# ArduinoDevBoardRevA.net
KiCad netlist of a schematic drawn in EAGLE
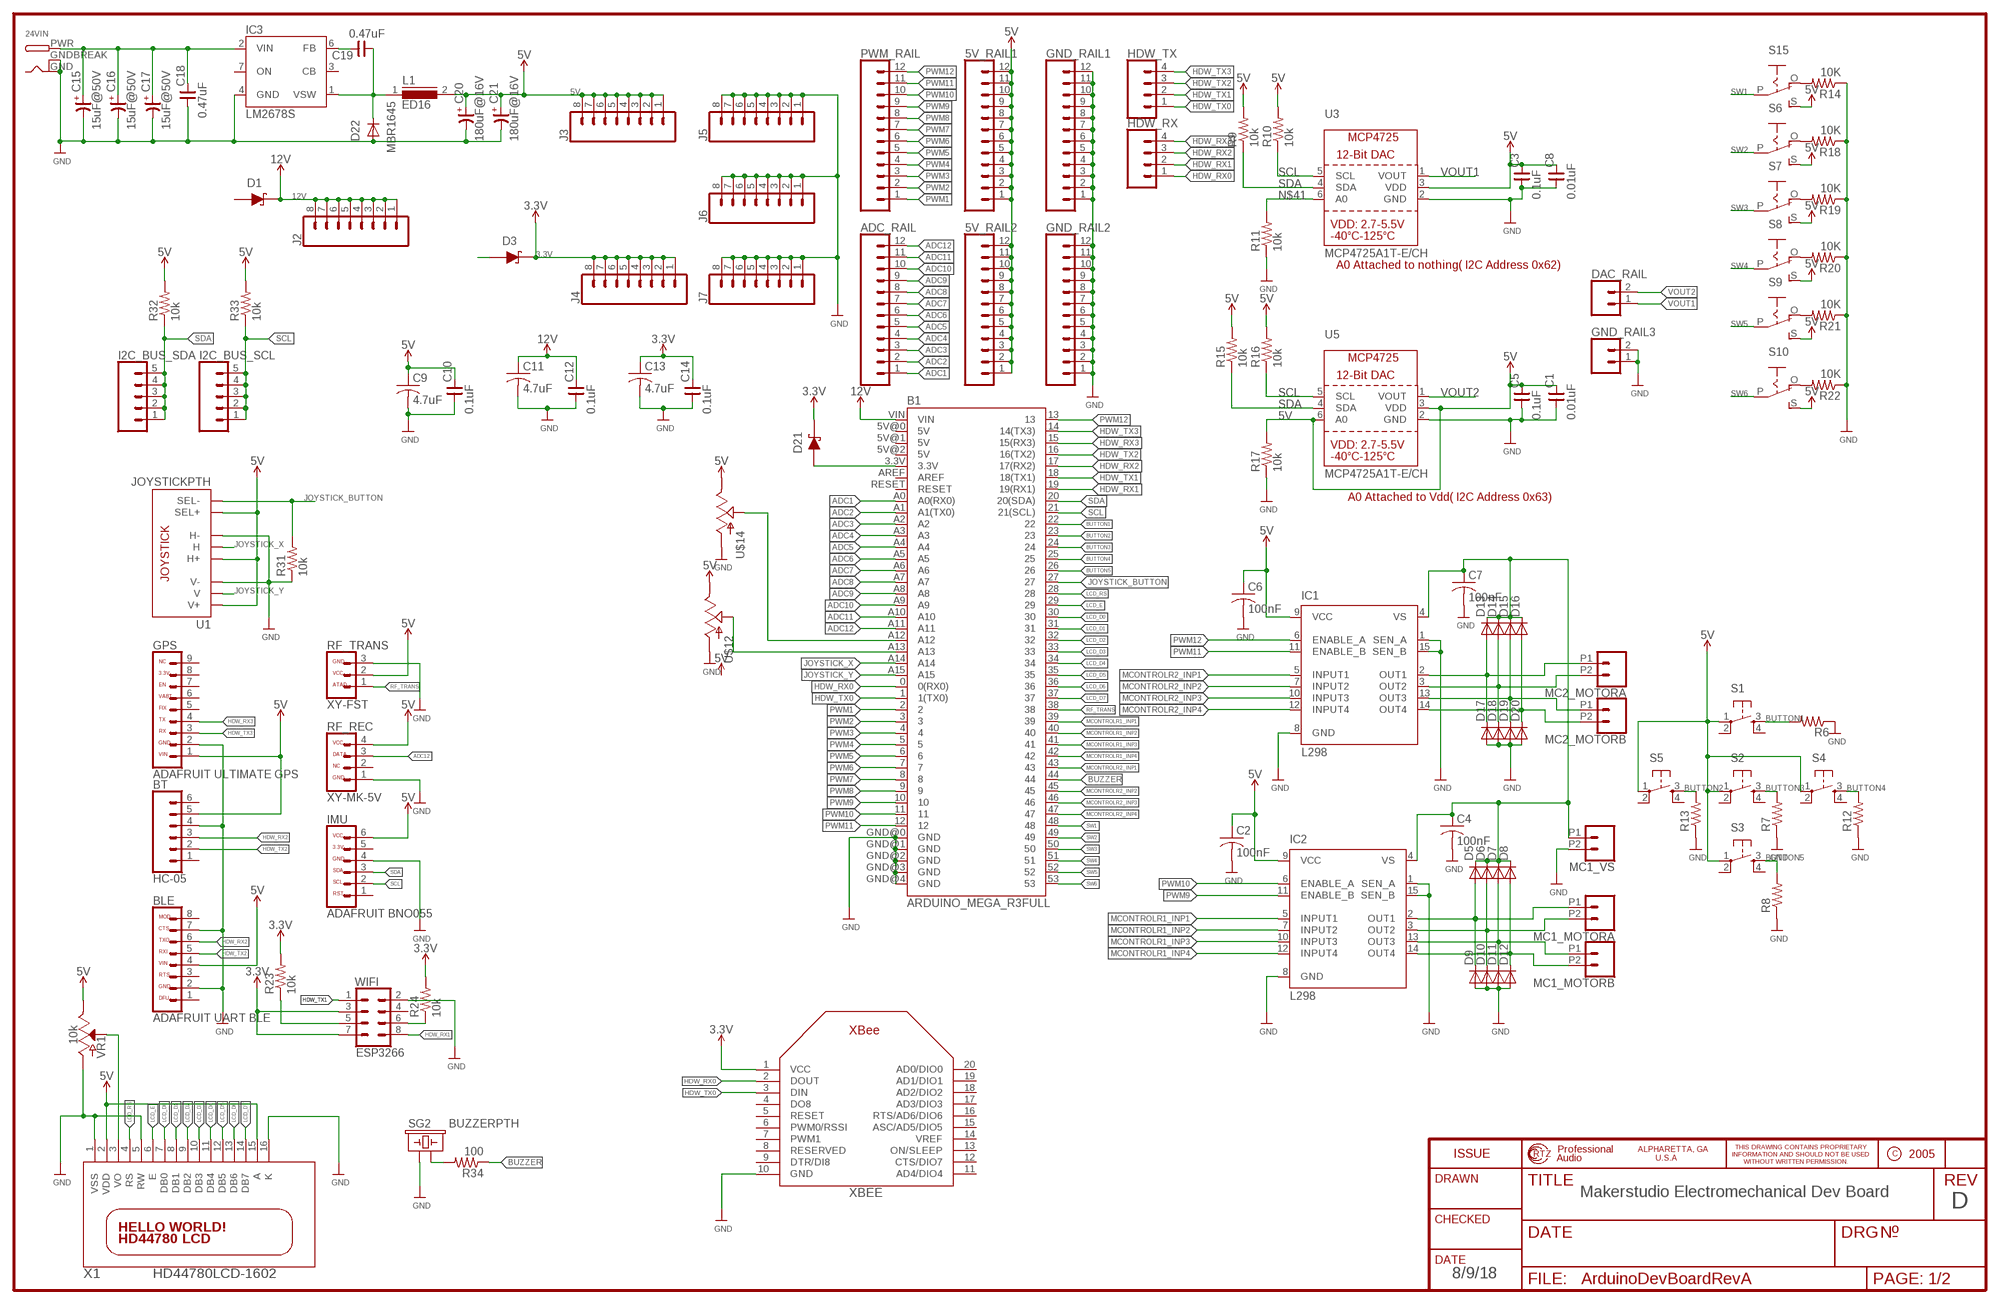
[diagram p0: schematic, sheet 1]
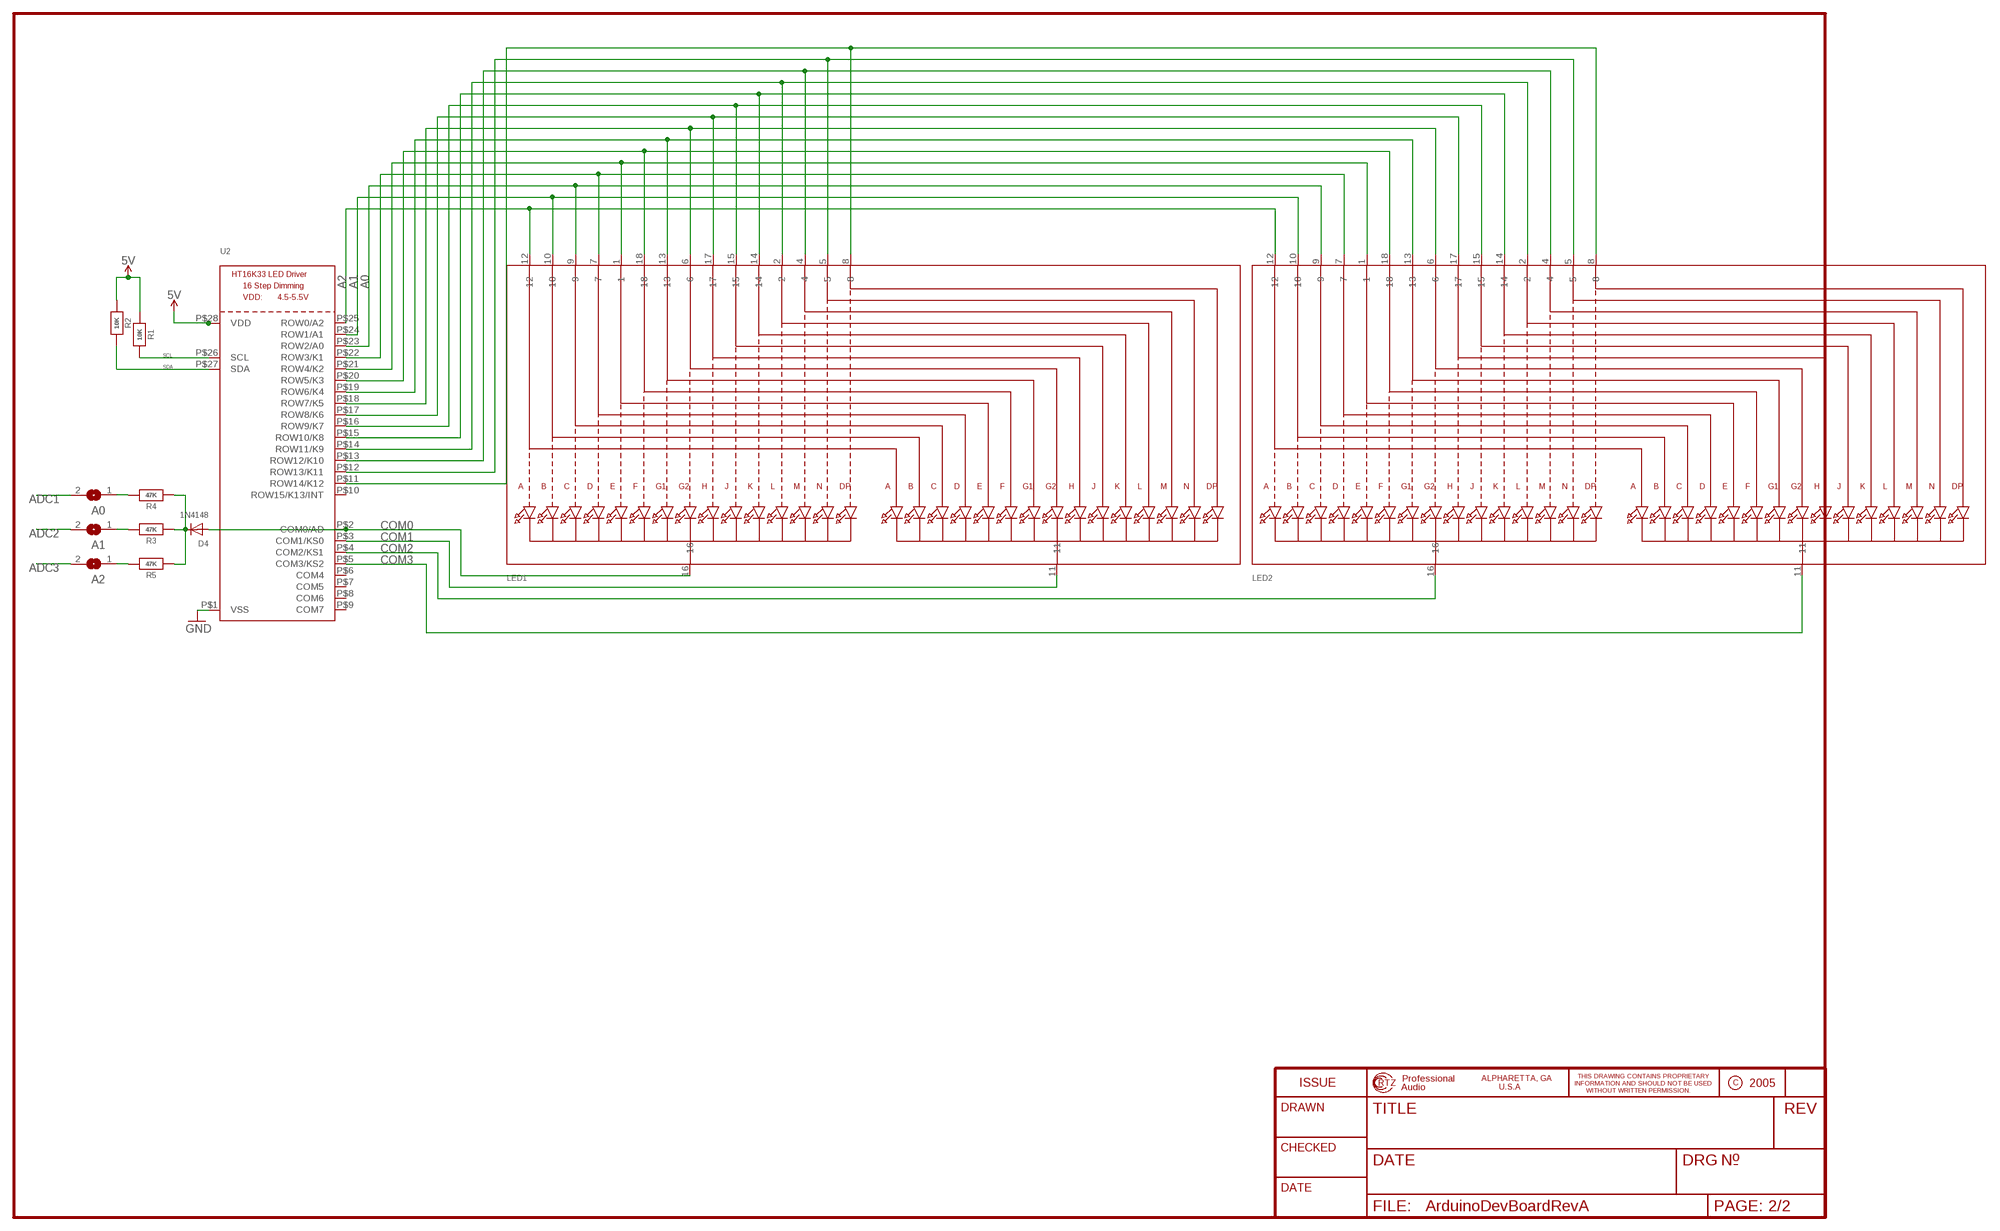
[diagram p1: schematic, sheet 2]

(export (version "E")
  (design (tool "Eeschema 10.0.6"))
  (components
    (comp (ref "5V_RAIL1")
      (value "CONN_12")
      (footprint "eagle-import:1X12")
      (libsource (lib "eagle-import") (part "CONN_12"))
    )
    (comp (ref "5V_RAIL2")
      (value "CONN_12")
      (footprint "eagle-import:1X12")
      (libsource (lib "eagle-import") (part "CONN_12"))
    )
    (comp (ref "24VIN")
      (value "DCBARRELPTH")
      (footprint "eagle-import:DCJACK_2MM_PTH")
      (libsource (lib "eagle-import") (part "DCBARRELPTH"))
    )
    (comp (ref "ADC_RAIL")
      (value "CONN_12")
      (footprint "eagle-import:1X12")
      (libsource (lib "eagle-import") (part "CONN_12"))
    )
    (comp (ref "B1")
      (value "ARDUINO_MEGA_R3FULL")
      (footprint "eagle-import:ARDUINO_MEGA")
      (libsource (lib "eagle-import") (part "ARDUINO_MEGA_R3FULL"))
    )
    (comp (ref "BLE")
      (value "ADAFRUIT UART BLE")
      (footprint "eagle-import:1X08")
      (libsource (lib "eagle-import") (part "CONN_08{dblquote}"))
    )
    (comp (ref "BT")
      (value "HC-05")
      (footprint "eagle-import:1X06")
      (libsource (lib "eagle-import") (part "CONN_06SILK_FEMALE_PTH"))
    )
    (comp (ref "C1")
      (value "0.01uF")
      (footprint "eagle-import:0805")
      (libsource (lib "eagle-import") (part "CNP-0805"))
    )
    (comp (ref "C2")
      (value "100nF")
      (footprint "eagle-import:C050-024X044")
      (libsource (lib "eagle-import") (part "C-US050-024X044"))
    )
    (comp (ref "C3")
      (value "0.1uF")
      (footprint "eagle-import:0805")
      (libsource (lib "eagle-import") (part "CNP-0805"))
    )
    (comp (ref "C4")
      (value "100nF")
      (footprint "eagle-import:C050-024X044")
      (libsource (lib "eagle-import") (part "C-US050-024X044"))
    )
    (comp (ref "C5")
      (value "0.1uF")
      (footprint "eagle-import:0805")
      (libsource (lib "eagle-import") (part "CNP-0805"))
    )
    (comp (ref "C6")
      (value "100nF")
      (footprint "eagle-import:C050-024X044")
      (libsource (lib "eagle-import") (part "C-US050-024X044"))
    )
    (comp (ref "C7")
      (value "100nF")
      (footprint "eagle-import:C050-024X044")
      (libsource (lib "eagle-import") (part "C-US050-024X044"))
    )
    (comp (ref "C8")
      (value "0.01uF")
      (footprint "eagle-import:0805")
      (libsource (lib "eagle-import") (part "CNP-0805"))
    )
    (comp (ref "C9")
      (value "4.7uF")
      (footprint "eagle-import:C050-024X044")
      (libsource (lib "eagle-import") (part "C-US050-024X044"))
    )
    (comp (ref "C10")
      (value "0.1uF")
      (footprint "eagle-import:0805")
      (libsource (lib "eagle-import") (part "CNP-0805"))
    )
    (comp (ref "C11")
      (value "4.7uF")
      (footprint "eagle-import:C0805")
      (libsource (lib "eagle-import") (part "C-USC0805"))
    )
    (comp (ref "C12")
      (value "0.1uF")
      (footprint "eagle-import:0805")
      (libsource (lib "eagle-import") (part "CNP-0805"))
    )
    (comp (ref "C13")
      (value "4.7uF")
      (footprint "eagle-import:C0805")
      (libsource (lib "eagle-import") (part "C-USC0805"))
    )
    (comp (ref "C14")
      (value "0.1uF")
      (footprint "eagle-import:0805")
      (libsource (lib "eagle-import") (part "CNP-0805"))
    )
    (comp (ref "C15")
      (value "15uF@50V")
      (footprint "eagle-import:E-025X065")
      (libsource (lib "eagle-import") (part "CP-E-025X065"))
    )
    (comp (ref "C16")
      (value "15uF@50V")
      (footprint "eagle-import:E-025X065")
      (libsource (lib "eagle-import") (part "CP-E-025X065"))
    )
    (comp (ref "C17")
      (value "15uF@50V")
      (footprint "eagle-import:E-025X065")
      (libsource (lib "eagle-import") (part "CP-E-025X065"))
    )
    (comp (ref "C18")
      (value "0.47uF")
      (footprint "eagle-import:0805")
      (libsource (lib "eagle-import") (part "CNP-0805"))
    )
    (comp (ref "C19")
      (value "0.47uF")
      (footprint "eagle-import:0805")
      (libsource (lib "eagle-import") (part "CNP-0805"))
    )
    (comp (ref "C20")
      (value "180uF@16V")
      (footprint "eagle-import:E-025X065")
      (libsource (lib "eagle-import") (part "CP-E-025X065"))
    )
    (comp (ref "C21")
      (value "180uF@16V")
      (footprint "eagle-import:E-025X065")
      (libsource (lib "eagle-import") (part "CP-E-025X065"))
    )
    (comp (ref "D1")
      (value "D_SCHOTTKYK")
      (footprint "eagle-import:SOD-123")
      (libsource (lib "eagle-import") (part "D_SCHOTTKYK"))
    )
    (comp (ref "D3")
      (value "D_SCHOTTKYK")
      (footprint "eagle-import:SOD-123")
      (libsource (lib "eagle-import") (part "D_SCHOTTKYK"))
    )
    (comp (ref "D5")
      (value "DIODE-D-5")
      (footprint "eagle-import:D-5")
      (libsource (lib "eagle-import") (part "DIODE-D-5"))
    )
    (comp (ref "D6")
      (value "DIODE-D-5")
      (footprint "eagle-import:D-5")
      (libsource (lib "eagle-import") (part "DIODE-D-5"))
    )
    (comp (ref "D7")
      (value "DIODE-D-5")
      (footprint "eagle-import:D-5")
      (libsource (lib "eagle-import") (part "DIODE-D-5"))
    )
    (comp (ref "D8")
      (value "DIODE-D-5")
      (footprint "eagle-import:D-5")
      (libsource (lib "eagle-import") (part "DIODE-D-5"))
    )
    (comp (ref "D9")
      (value "DIODE-D-5")
      (footprint "eagle-import:D-5")
      (libsource (lib "eagle-import") (part "DIODE-D-5"))
    )
    (comp (ref "D10")
      (value "DIODE-D-5")
      (footprint "eagle-import:D-5")
      (libsource (lib "eagle-import") (part "DIODE-D-5"))
    )
    (comp (ref "D11")
      (value "DIODE-D-5")
      (footprint "eagle-import:D-5")
      (libsource (lib "eagle-import") (part "DIODE-D-5"))
    )
    (comp (ref "D12")
      (value "DIODE-D-5")
      (footprint "eagle-import:D-5")
      (libsource (lib "eagle-import") (part "DIODE-D-5"))
    )
    (comp (ref "D13")
      (value "DIODE-D-5")
      (footprint "eagle-import:D-5")
      (libsource (lib "eagle-import") (part "DIODE-D-5"))
    )
    (comp (ref "D14")
      (value "DIODE-D-5")
      (footprint "eagle-import:D-5")
      (libsource (lib "eagle-import") (part "DIODE-D-5"))
    )
    (comp (ref "D15")
      (value "DIODE-D-5")
      (footprint "eagle-import:D-5")
      (libsource (lib "eagle-import") (part "DIODE-D-5"))
    )
    (comp (ref "D16")
      (value "DIODE-D-5")
      (footprint "eagle-import:D-5")
      (libsource (lib "eagle-import") (part "DIODE-D-5"))
    )
    (comp (ref "D17")
      (value "DIODE-D-5")
      (footprint "eagle-import:D-5")
      (libsource (lib "eagle-import") (part "DIODE-D-5"))
    )
    (comp (ref "D18")
      (value "DIODE-D-5")
      (footprint "eagle-import:D-5")
      (libsource (lib "eagle-import") (part "DIODE-D-5"))
    )
    (comp (ref "D19")
      (value "DIODE-D-5")
      (footprint "eagle-import:D-5")
      (libsource (lib "eagle-import") (part "DIODE-D-5"))
    )
    (comp (ref "D20")
      (value "DIODE-D-5")
      (footprint "eagle-import:D-5")
      (libsource (lib "eagle-import") (part "DIODE-D-5"))
    )
    (comp (ref "D21")
      (value "D_SCHOTTKYK")
      (footprint "eagle-import:SOD-123")
      (libsource (lib "eagle-import") (part "D_SCHOTTKYK"))
    )
    (comp (ref "D22")
      (value "MBR1645")
      (footprint "eagle-import:TO220AC")
      (libsource (lib "eagle-import") (part "MBR750"))
    )
    (comp (ref "DAC_RAIL")
      (value "CONN_02")
      (footprint "eagle-import:1X02")
      (libsource (lib "eagle-import") (part "CONN_02"))
    )
    (comp (ref "GND_RAIL1")
      (value "CONN_12")
      (footprint "eagle-import:1X12")
      (libsource (lib "eagle-import") (part "CONN_12"))
    )
    (comp (ref "GND_RAIL2")
      (value "CONN_12")
      (footprint "eagle-import:1X12")
      (libsource (lib "eagle-import") (part "CONN_12"))
    )
    (comp (ref "GND_RAIL3")
      (value "CONN_02")
      (footprint "eagle-import:1X02")
      (libsource (lib "eagle-import") (part "CONN_02"))
    )
    (comp (ref "GPS")
      (value "ADAFRUIT ULTIMATE GPS")
      (footprint "eagle-import:1X09")
      (libsource (lib "eagle-import") (part "CONN_09"))
    )
    (comp (ref "HDW_RX")
      (value "CONN_04")
      (footprint "eagle-import:1X04")
      (libsource (lib "eagle-import") (part "SparkFun-Connectors_513_CONN_04"))
    )
    (comp (ref "HDW_TX")
      (value "CONN_04")
      (footprint "eagle-import:1X04")
      (libsource (lib "eagle-import") (part "SparkFun-Connectors_513_CONN_04"))
    )
    (comp (ref "I2C_BUS_SCL")
      (value "CONN_05")
      (footprint "eagle-import:1X05")
      (libsource (lib "eagle-import") (part "CONN_05"))
    )
    (comp (ref "I2C_BUS_SDA")
      (value "CONN_05")
      (footprint "eagle-import:1X05")
      (libsource (lib "eagle-import") (part "CONN_05"))
    )
    (comp (ref "IC1")
      (value "L298")
      (footprint "eagle-import:MULTIWATT-15")
      (fields (field (name "MPN") "L298N"))
      (libsource (lib "eagle-import") (part "L298"))
    )
    (comp (ref "IC2")
      (value "L298")
      (footprint "eagle-import:MULTIWATT-15")
      (fields (field (name "MPN") "L298N"))
      (libsource (lib "eagle-import") (part "L298"))
    )
    (comp (ref "IC3")
      (value "LM2678S")
      (footprint "eagle-import:TO263-7")
      (libsource (lib "eagle-import") (part "LM2678S"))
    )
    (comp (ref "IMU")
      (value "ADAFRUIT BNO055")
      (footprint "eagle-import:1X06")
      (libsource (lib "eagle-import") (part "SparkFun-Connectors_513_CONN_06SILK_FEMALE_PTH"))
    )
    (comp (ref "J2")
      (value "CONN_08\"")
      (footprint "eagle-import:1X08")
      (libsource (lib "eagle-import") (part "CONN_08{dblquote}"))
    )
    (comp (ref "J3")
      (value "CONN_08\"")
      (footprint "eagle-import:1X08")
      (libsource (lib "eagle-import") (part "CONN_08{dblquote}"))
    )
    (comp (ref "J4")
      (value "CONN_08\"")
      (footprint "eagle-import:1X08")
      (libsource (lib "eagle-import") (part "CONN_08{dblquote}"))
    )
    (comp (ref "J5")
      (value "CONN_08\"")
      (footprint "eagle-import:1X08")
      (libsource (lib "eagle-import") (part "CONN_08{dblquote}"))
    )
    (comp (ref "J6")
      (value "CONN_08\"")
      (footprint "eagle-import:1X08")
      (libsource (lib "eagle-import") (part "CONN_08{dblquote}"))
    )
    (comp (ref "J7")
      (value "CONN_08\"")
      (footprint "eagle-import:1X08")
      (libsource (lib "eagle-import") (part "CONN_08{dblquote}"))
    )
    (comp (ref "L1")
      (value "ED16")
      (footprint "eagle-import:ED16")
      (libsource (lib "eagle-import") (part "ED16"))
    )
    (comp (ref "MC1_MOTORA")
      (value "CONN_022.54MM_SCREWTERM")
      (footprint "eagle-import:1X02_2.54_SCREWTERM")
      (libsource (lib "eagle-import") (part "CONN_022.54MM_SCREWTERM"))
    )
    (comp (ref "MC1_MOTORB")
      (value "CONN_022.54MM_SCREWTERM")
      (footprint "eagle-import:1X02_2.54_SCREWTERM")
      (libsource (lib "eagle-import") (part "CONN_022.54MM_SCREWTERM"))
    )
    (comp (ref "MC1_VS")
      (value "CONN_022.54MM_SCREWTERM")
      (footprint "eagle-import:1X02_2.54_SCREWTERM")
      (libsource (lib "eagle-import") (part "CONN_022.54MM_SCREWTERM"))
    )
    (comp (ref "MC2_MOTORA")
      (value "CONN_022.54MM_SCREWTERM")
      (footprint "eagle-import:1X02_2.54_SCREWTERM")
      (libsource (lib "eagle-import") (part "CONN_022.54MM_SCREWTERM"))
    )
    (comp (ref "MC2_MOTORB")
      (value "CONN_022.54MM_SCREWTERM")
      (footprint "eagle-import:1X02_2.54_SCREWTERM")
      (libsource (lib "eagle-import") (part "CONN_022.54MM_SCREWTERM"))
    )
    (comp (ref "PWM_RAIL")
      (value "CONN_12")
      (footprint "eagle-import:1X12")
      (libsource (lib "eagle-import") (part "CONN_12"))
    )
    (comp (ref "R6")
      (value "R-US_R0805")
      (footprint "eagle-import:R0805")
      (libsource (lib "eagle-import") (part "R-US_R0805"))
    )
    (comp (ref "R7")
      (value "R-US_R0805")
      (footprint "eagle-import:R0805")
      (libsource (lib "eagle-import") (part "R-US_R0805"))
    )
    (comp (ref "R8")
      (value "R-US_R0805")
      (footprint "eagle-import:R0805")
      (libsource (lib "eagle-import") (part "R-US_R0805"))
    )
    (comp (ref "R9")
      (value "10k")
      (footprint "eagle-import:R0805")
      (libsource (lib "eagle-import") (part "R-US_R0805"))
    )
    (comp (ref "R10")
      (value "10k")
      (footprint "eagle-import:R0805")
      (libsource (lib "eagle-import") (part "R-US_R0805"))
    )
    (comp (ref "R11")
      (value "10k")
      (footprint "eagle-import:R0805")
      (libsource (lib "eagle-import") (part "R-US_R0805"))
    )
    (comp (ref "R12")
      (value "R-US_R0805")
      (footprint "eagle-import:R0805")
      (libsource (lib "eagle-import") (part "R-US_R0805"))
    )
    (comp (ref "R13")
      (value "R-US_R0805")
      (footprint "eagle-import:R0805")
      (libsource (lib "eagle-import") (part "R-US_R0805"))
    )
    (comp (ref "R14")
      (value "10K")
      (footprint "eagle-import:R0805")
      (libsource (lib "eagle-import") (part "R-US_R0805"))
    )
    (comp (ref "R15")
      (value "10k")
      (footprint "eagle-import:R0805")
      (libsource (lib "eagle-import") (part "R-US_R0805"))
    )
    (comp (ref "R16")
      (value "10k")
      (footprint "eagle-import:R0805")
      (libsource (lib "eagle-import") (part "R-US_R0805"))
    )
    (comp (ref "R17")
      (value "10k")
      (footprint "eagle-import:R0805")
      (libsource (lib "eagle-import") (part "R-US_R0805"))
    )
    (comp (ref "R18")
      (value "10K")
      (footprint "eagle-import:R0805")
      (libsource (lib "eagle-import") (part "R-US_R0805"))
    )
    (comp (ref "R19")
      (value "10K")
      (footprint "eagle-import:R0805")
      (libsource (lib "eagle-import") (part "R-US_R0805"))
    )
    (comp (ref "R20")
      (value "10K")
      (footprint "eagle-import:R0805")
      (libsource (lib "eagle-import") (part "R-US_R0805"))
    )
    (comp (ref "R21")
      (value "10K")
      (footprint "eagle-import:R0805")
      (libsource (lib "eagle-import") (part "R-US_R0805"))
    )
    (comp (ref "R22")
      (value "10K")
      (footprint "eagle-import:R0805")
      (libsource (lib "eagle-import") (part "R-US_R0805"))
    )
    (comp (ref "R23")
      (value "10k")
      (footprint "eagle-import:R0805")
      (libsource (lib "eagle-import") (part "R-US_R0805"))
    )
    (comp (ref "R24")
      (value "10k")
      (footprint "eagle-import:R0805")
      (libsource (lib "eagle-import") (part "R-US_R0805"))
    )
    (comp (ref "R31")
      (value "10k")
      (footprint "eagle-import:R0805")
      (libsource (lib "eagle-import") (part "R-US_R0805"))
    )
    (comp (ref "R32")
      (value "10k")
      (footprint "eagle-import:R0805")
      (libsource (lib "eagle-import") (part "R-US_R0805"))
    )
    (comp (ref "R33")
      (value "10k")
      (footprint "eagle-import:R0805")
      (libsource (lib "eagle-import") (part "R-US_R0805"))
    )
    (comp (ref "R34")
      (value "100")
      (footprint "eagle-import:R0805")
      (libsource (lib "eagle-import") (part "R-US_R0805"))
    )
    (comp (ref "RF_REC")
      (value "XY-MK-5V")
      (footprint "eagle-import:1X04")
      (libsource (lib "eagle-import") (part "CONN_04"))
    )
    (comp (ref "RF_TRANS")
      (value "XY-FST")
      (footprint "eagle-import:1X03")
      (libsource (lib "eagle-import") (part "CONN_03"))
    )
    (comp (ref "S1")
      (value "TAC_SWITCHSMD")
      (footprint "eagle-import:TACTILE_SWITCH_SMD")
      (libsource (lib "eagle-import") (part "TAC_SWITCHSMD"))
    )
    (comp (ref "S2")
      (value "TAC_SWITCHSMD")
      (footprint "eagle-import:TACTILE_SWITCH_SMD")
      (libsource (lib "eagle-import") (part "TAC_SWITCHSMD"))
    )
    (comp (ref "S3")
      (value "TAC_SWITCHSMD")
      (footprint "eagle-import:TACTILE_SWITCH_SMD")
      (libsource (lib "eagle-import") (part "TAC_SWITCHSMD"))
    )
    (comp (ref "S4")
      (value "TAC_SWITCHSMD")
      (footprint "eagle-import:TACTILE_SWITCH_SMD")
      (libsource (lib "eagle-import") (part "TAC_SWITCHSMD"))
    )
    (comp (ref "S5")
      (value "TAC_SWITCHSMD")
      (footprint "eagle-import:TACTILE_SWITCH_SMD")
      (libsource (lib "eagle-import") (part "TAC_SWITCHSMD"))
    )
    (comp (ref "S6")
      (value "EG1218S")
      (footprint "eagle-import:EG1218")
      (libsource (lib "eagle-import") (part "EG1218S"))
    )
    (comp (ref "S7")
      (value "EG1218S")
      (footprint "eagle-import:EG1218")
      (libsource (lib "eagle-import") (part "EG1218S"))
    )
    (comp (ref "S8")
      (value "EG1218S")
      (footprint "eagle-import:EG1218")
      (libsource (lib "eagle-import") (part "EG1218S"))
    )
    (comp (ref "S9")
      (value "EG1218S")
      (footprint "eagle-import:EG1218")
      (libsource (lib "eagle-import") (part "EG1218S"))
    )
    (comp (ref "S10")
      (value "EG1218S")
      (footprint "eagle-import:EG1218")
      (libsource (lib "eagle-import") (part "EG1218S"))
    )
    (comp (ref "S15")
      (value "EG1218S")
      (footprint "eagle-import:EG1218")
      (libsource (lib "eagle-import") (part "EG1218S"))
    )
    (comp (ref "SG2")
      (value "BUZZERPTH")
      (footprint "eagle-import:BUZZER-12MM")
      (libsource (lib "eagle-import") (part "BUZZERPTH"))
    )
    (comp (ref "U$12")
      (value "POT")
      (footprint "eagle-import:ALPS_POT")
      (libsource (lib "eagle-import") (part "POT"))
    )
    (comp (ref "U$14")
      (value "POT")
      (footprint "eagle-import:ALPS_POT")
      (libsource (lib "eagle-import") (part "POT"))
    )
    (comp (ref "U1")
      (value "JOYSTICKPTH")
      (footprint "eagle-import:JOYSTICK")
      (libsource (lib "eagle-import") (part "JOYSTICKPTH"))
    )
    (comp (ref "U3")
      (value "MCP4725A1T-E/CH")
      (footprint "eagle-import:SOT23-6")
      (libsource (lib "eagle-import") (part "DAC_MCP4725"))
    )
    (comp (ref "U5")
      (value "MCP4725A1T-E/CH")
      (footprint "eagle-import:SOT23-6")
      (libsource (lib "eagle-import") (part "DAC_MCP4725"))
    )
    (comp (ref "VR1")
      (value "10k")
      (footprint "eagle-import:POT-PTH-ALPS-KIT")
      (libsource (lib "eagle-import") (part "POTENTIOMETER-PTH-9MM-1/20W-20%-KIT"))
    )
    (comp (ref "WIFI")
      (value "ESP3266")
      (footprint "eagle-import:2X4")
      (libsource (lib "eagle-import") (part "CONN_04X2"))
    )
    (comp (ref "X1")
      (value "HD44780LCD-1602")
      (footprint "eagle-import:LCD1602")
      (libsource (lib "eagle-import") (part "HD44780LCD-1602"))
    )
    (comp (ref "XBEE")
      (value "XBEE")
      (footprint "eagle-import:XBEE")
      (libsource (lib "eagle-import") (part "XBEE"))
    )
    (comp (ref "A0")
      (value "SOLDERJUMPERREFLOW_NOPASTE")
      (footprint "eagle-import:SOLDERJUMPER_REFLOW_NOPASTE")
      (libsource (lib "eagle-import") (part "SOLDERJUMPERREFLOW_NOPASTE"))
    )
    (comp (ref "A1")
      (value "SOLDERJUMPERREFLOW_NOPASTE")
      (footprint "eagle-import:SOLDERJUMPER_REFLOW_NOPASTE")
      (libsource (lib "eagle-import") (part "SOLDERJUMPERREFLOW_NOPASTE"))
    )
    (comp (ref "A2")
      (value "SOLDERJUMPERREFLOW_NOPASTE")
      (footprint "eagle-import:SOLDERJUMPER_REFLOW_NOPASTE")
      (libsource (lib "eagle-import") (part "SOLDERJUMPERREFLOW_NOPASTE"))
    )
    (comp (ref "D4")
      (value "1N4148")
      (footprint "eagle-import:SOD-323F")
      (libsource (lib "eagle-import") (part "DIODESOD-323F"))
    )
    (comp (ref "LED1")
      (value "DISP_SEGMENT_STARBURST_DUAL_COMMONCATHODE")
      (footprint "eagle-import:SEGMENT_STARTBUST_DUAL_KWA-541CBB")
      (libsource (lib "eagle-import") (part "DISP_SEGMENT_STARBURST_DUAL_COMMONCATHODE"))
    )
    (comp (ref "LED2")
      (value "DISP_SEGMENT_STARBURST_DUAL_COMMONCATHODE")
      (footprint "eagle-import:SEGMENT_STARTBUST_DUAL_KWA-541CBB")
      (libsource (lib "eagle-import") (part "DISP_SEGMENT_STARBURST_DUAL_COMMONCATHODE"))
    )
    (comp (ref "R1")
      (value "10K")
      (footprint "eagle-import:0805-NO")
      (libsource (lib "eagle-import") (part "RESISTOR0805_NOOUTLINE"))
    )
    (comp (ref "R2")
      (value "10K")
      (footprint "eagle-import:0805-NO")
      (libsource (lib "eagle-import") (part "RESISTOR0805_NOOUTLINE"))
    )
    (comp (ref "R3")
      (value "47K")
      (footprint "eagle-import:0805-NO")
      (libsource (lib "eagle-import") (part "RESISTOR0805_NOOUTLINE"))
    )
    (comp (ref "R4")
      (value "47K")
      (footprint "eagle-import:0805-NO")
      (libsource (lib "eagle-import") (part "RESISTOR0805_NOOUTLINE"))
    )
    (comp (ref "R5")
      (value "47K")
      (footprint "eagle-import:0805-NO")
      (libsource (lib "eagle-import") (part "RESISTOR0805_NOOUTLINE"))
    )
    (comp (ref "U2")
      (value "HT16K33_SOP28")
      (footprint "eagle-import:SOP28_300MIL")
      (libsource (lib "eagle-import") (part "HT16K33_SOP28"))
    )
  )
  (nets
    (net (code "1") (name "3.3V") (class "Default")
      (node (ref "C13") (pin "1") (pinfunction "1_1") (pintype "passive"))
      (node (ref "C14") (pin "2") (pinfunction "2_2") (pintype "passive"))
      (node (ref "D21") (pin "2") (pinfunction "C_2") (pintype "passive"))
      (node (ref "D3") (pin "2") (pinfunction "C_2") (pintype "passive"))
      (node (ref "J4") (pin "1") (pinfunction "1_1") (pintype "passive"))
      (node (ref "J4") (pin "2") (pinfunction "2_2") (pintype "passive"))
      (node (ref "J4") (pin "3") (pinfunction "3_3") (pintype "passive"))
      (node (ref "J4") (pin "4") (pinfunction "4_4") (pintype "passive"))
      (node (ref "J4") (pin "5") (pinfunction "5_5") (pintype "passive"))
      (node (ref "J4") (pin "6") (pinfunction "6_6") (pintype "passive"))
      (node (ref "J4") (pin "7") (pinfunction "7_7") (pintype "passive"))
      (node (ref "J4") (pin "8") (pinfunction "8_8") (pintype "passive"))
      (node (ref "R23") (pin "2") (pinfunction "2_2") (pintype "passive"))
      (node (ref "R24") (pin "2") (pinfunction "2_2") (pintype "passive"))
      (node (ref "WIFI") (pin "3") (pinfunction "3_3") (pintype "passive"))
      (node (ref "WIFI") (pin "7") (pinfunction "7_7") (pintype "passive"))
      (node (ref "XBEE") (pin "1") (pinfunction "VCC_1") (pintype "power_in"))
    )
    (net (code "2") (name "5V") (class "Default")
      (node (ref "5V_RAIL1") (pin "1") (pinfunction "1_1") (pintype "passive"))
      (node (ref "5V_RAIL1") (pin "10") (pinfunction "10_10") (pintype "passive"))
      (node (ref "5V_RAIL1") (pin "11") (pinfunction "11_11") (pintype "passive"))
      (node (ref "5V_RAIL1") (pin "12") (pinfunction "12_12") (pintype "passive"))
      (node (ref "5V_RAIL1") (pin "2") (pinfunction "2_2") (pintype "passive"))
      (node (ref "5V_RAIL1") (pin "3") (pinfunction "3_3") (pintype "passive"))
      (node (ref "5V_RAIL1") (pin "4") (pinfunction "4_4") (pintype "passive"))
      (node (ref "5V_RAIL1") (pin "5") (pinfunction "5_5") (pintype "passive"))
      (node (ref "5V_RAIL1") (pin "6") (pinfunction "6_6") (pintype "passive"))
      (node (ref "5V_RAIL1") (pin "7") (pinfunction "7_7") (pintype "passive"))
      (node (ref "5V_RAIL1") (pin "8") (pinfunction "8_8") (pintype "passive"))
      (node (ref "5V_RAIL1") (pin "9") (pinfunction "9_9") (pintype "passive"))
      (node (ref "5V_RAIL2") (pin "1") (pinfunction "1_1") (pintype "passive"))
      (node (ref "5V_RAIL2") (pin "10") (pinfunction "10_10") (pintype "passive"))
      (node (ref "5V_RAIL2") (pin "11") (pinfunction "11_11") (pintype "passive"))
      (node (ref "5V_RAIL2") (pin "12") (pinfunction "12_12") (pintype "passive"))
      (node (ref "5V_RAIL2") (pin "2") (pinfunction "2_2") (pintype "passive"))
      (node (ref "5V_RAIL2") (pin "3") (pinfunction "3_3") (pintype "passive"))
      (node (ref "5V_RAIL2") (pin "4") (pinfunction "4_4") (pintype "passive"))
      (node (ref "5V_RAIL2") (pin "5") (pinfunction "5_5") (pintype "passive"))
      (node (ref "5V_RAIL2") (pin "6") (pinfunction "6_6") (pintype "passive"))
      (node (ref "5V_RAIL2") (pin "7") (pinfunction "7_7") (pintype "passive"))
      (node (ref "5V_RAIL2") (pin "8") (pinfunction "8_8") (pintype "passive"))
      (node (ref "5V_RAIL2") (pin "9") (pinfunction "9_9") (pintype "passive"))
      (node (ref "BLE") (pin "4") (pinfunction "4_4") (pintype "passive"))
      (node (ref "BT") (pin "5") (pinfunction "5_5") (pintype "passive"))
      (node (ref "C1") (pin "2") (pinfunction "2_2") (pintype "passive"))
      (node (ref "C10") (pin "2") (pinfunction "2_2") (pintype "passive"))
      (node (ref "C2") (pin "1") (pinfunction "1_1") (pintype "passive"))
      (node (ref "C20") (pin "+") (pinfunction "+_+") (pintype "passive"))
      (node (ref "C21") (pin "+") (pinfunction "+_+") (pintype "passive"))
      (node (ref "C3") (pin "2") (pinfunction "2_2") (pintype "passive"))
      (node (ref "C5") (pin "2") (pinfunction "2_2") (pintype "passive"))
      (node (ref "C6") (pin "1") (pinfunction "1_1") (pintype "passive"))
      (node (ref "C8") (pin "2") (pinfunction "2_2") (pintype "passive"))
      (node (ref "C9") (pin "1") (pinfunction "1_1") (pintype "passive"))
      (node (ref "GPS") (pin "1") (pinfunction "1_1") (pintype "passive"))
      (node (ref "IC1") (pin "9") (pinfunction "VCC_9") (pintype "power_in"))
      (node (ref "IC2") (pin "9") (pinfunction "VCC_9") (pintype "power_in"))
      (node (ref "IMU") (pin "6") (pinfunction "6_6") (pintype "passive"))
      (node (ref "J3") (pin "1") (pinfunction "1_1") (pintype "passive"))
      (node (ref "J3") (pin "2") (pinfunction "2_2") (pintype "passive"))
      (node (ref "J3") (pin "3") (pinfunction "3_3") (pintype "passive"))
      (node (ref "J3") (pin "4") (pinfunction "4_4") (pintype "passive"))
      (node (ref "J3") (pin "5") (pinfunction "5_5") (pintype "passive"))
      (node (ref "J3") (pin "6") (pinfunction "6_6") (pintype "passive"))
      (node (ref "J3") (pin "7") (pinfunction "7_7") (pintype "passive"))
      (node (ref "J3") (pin "8") (pinfunction "8_8") (pintype "passive"))
      (node (ref "L1") (pin "2") (pinfunction "2_2") (pintype "passive"))
      (node (ref "R1") (pin "1") (pinfunction "1_1") (pintype "passive"))
      (node (ref "R10") (pin "2") (pinfunction "2_2") (pintype "passive"))
      (node (ref "R15") (pin "2") (pinfunction "2_2") (pintype "passive"))
      (node (ref "R16") (pin "2") (pinfunction "2_2") (pintype "passive"))
      (node (ref "R17") (pin "2") (pinfunction "2_2") (pintype "passive"))
      (node (ref "R2") (pin "1") (pinfunction "1_1") (pintype "passive"))
      (node (ref "R32") (pin "2") (pinfunction "2_2") (pintype "passive"))
      (node (ref "R33") (pin "2") (pinfunction "2_2") (pintype "passive"))
      (node (ref "R9") (pin "2") (pinfunction "2_2") (pintype "passive"))
      (node (ref "RF_REC") (pin "4") (pinfunction "4_4") (pintype "passive"))
      (node (ref "RF_TRANS") (pin "2") (pinfunction "2_2") (pintype "passive"))
      (node (ref "S1") (pin "1") (pinfunction "1_1") (pintype "passive"))
      (node (ref "S10") (pin "S") (pinfunction "S_S") (pintype "passive"))
      (node (ref "S15") (pin "S") (pinfunction "S_S") (pintype "passive"))
      (node (ref "S2") (pin "1") (pinfunction "1_1") (pintype "passive"))
      (node (ref "S3") (pin "1") (pinfunction "1_1") (pintype "passive"))
      (node (ref "S4") (pin "1") (pinfunction "1_1") (pintype "passive"))
      (node (ref "S5") (pin "1") (pinfunction "1_1") (pintype "passive"))
      (node (ref "S6") (pin "S") (pinfunction "S_S") (pintype "passive"))
      (node (ref "S7") (pin "S") (pinfunction "S_S") (pintype "passive"))
      (node (ref "S8") (pin "S") (pinfunction "S_S") (pintype "passive"))
      (node (ref "S9") (pin "S") (pinfunction "S_S") (pintype "passive"))
      (node (ref "U$12") (pin "P$1") (pinfunction "E_P$1") (pintype "passive"))
      (node (ref "U$14") (pin "P$1") (pinfunction "E_P$1") (pintype "passive"))
      (node (ref "U1") (pin "B1A") (pinfunction "SEL+_B1A") (pintype "bidirectional"))
      (node (ref "U1") (pin "H1") (pinfunction "H+_H1") (pintype "bidirectional"))
      (node (ref "U1") (pin "V1") (pinfunction "V+_V1") (pintype "bidirectional"))
      (node (ref "U2") (pin "P$28") (pinfunction "VDD_P$28") (pintype "bidirectional"))
      (node (ref "U3") (pin "3") (pinfunction "VDD_3") (pintype "power_in"))
      (node (ref "U5") (pin "3") (pinfunction "VDD_3") (pintype "power_in"))
      (node (ref "U5") (pin "6") (pinfunction "A0_6") (pintype "input"))
      (node (ref "VR1") (pin "P$1") (pinfunction "E_P$1") (pintype "passive"))
      (node (ref "X1") (pin "15") (pinfunction "A_15") (pintype "input"))
      (node (ref "X1") (pin "2") (pinfunction "VDD_2") (pintype "power_in"))
    )
    (net (code "3") (name "12V") (class "Default")
      (node (ref "B1") (pin "VIN") (pinfunction "VIN_VIN") (pintype "bidirectional"))
      (node (ref "C11") (pin "1") (pinfunction "1_1") (pintype "passive"))
      (node (ref "C12") (pin "2") (pinfunction "2_2") (pintype "passive"))
      (node (ref "D1") (pin "2") (pinfunction "C_2") (pintype "passive"))
      (node (ref "J2") (pin "1") (pinfunction "1_1") (pintype "passive"))
      (node (ref "J2") (pin "2") (pinfunction "2_2") (pintype "passive"))
      (node (ref "J2") (pin "3") (pinfunction "3_3") (pintype "passive"))
      (node (ref "J2") (pin "4") (pinfunction "4_4") (pintype "passive"))
      (node (ref "J2") (pin "5") (pinfunction "5_5") (pintype "passive"))
      (node (ref "J2") (pin "6") (pinfunction "6_6") (pintype "passive"))
      (node (ref "J2") (pin "7") (pinfunction "7_7") (pintype "passive"))
      (node (ref "J2") (pin "8") (pinfunction "8_8") (pintype "passive"))
    )
    (net (code "4") (name "A0") (class "Default")
      (node (ref "LED1") (pin "9") (pinfunction "9_9") (pintype "bidirectional"))
      (node (ref "LED2") (pin "9") (pinfunction "9_9") (pintype "bidirectional"))
      (node (ref "U2") (pin "P$23") (pinfunction "ROW2/A0_P$23") (pintype "bidirectional"))
    )
    (net (code "5") (name "A1") (class "Default")
      (node (ref "LED1") (pin "10") (pinfunction "10_10") (pintype "bidirectional"))
      (node (ref "LED2") (pin "10") (pinfunction "10_10") (pintype "bidirectional"))
      (node (ref "U2") (pin "P$24") (pinfunction "ROW1/A1_P$24") (pintype "bidirectional"))
    )
    (net (code "6") (name "A2") (class "Default")
      (node (ref "LED1") (pin "12") (pinfunction "12_12") (pintype "bidirectional"))
      (node (ref "LED2") (pin "12") (pinfunction "12_12") (pintype "bidirectional"))
      (node (ref "U2") (pin "P$25") (pinfunction "ROW0/A2_P$25") (pintype "bidirectional"))
    )
    (net (code "7") (name "ADC1") (class "Default")
      (node (ref "A0") (pin "2") (pinfunction "2_2") (pintype "passive"))
      (node (ref "ADC_RAIL") (pin "1") (pinfunction "1_1") (pintype "passive"))
      (node (ref "B1") (pin "A0") (pinfunction "A0(RX0)_A0") (pintype "bidirectional"))
    )
    (net (code "8") (name "ADC2") (class "Default")
      (node (ref "A1") (pin "2") (pinfunction "2_2") (pintype "passive"))
      (node (ref "ADC_RAIL") (pin "2") (pinfunction "2_2") (pintype "passive"))
      (node (ref "B1") (pin "A1") (pinfunction "A1(TX0)_A1") (pintype "bidirectional"))
    )
    (net (code "9") (name "ADC3") (class "Default")
      (node (ref "A2") (pin "2") (pinfunction "2_2") (pintype "passive"))
      (node (ref "ADC_RAIL") (pin "3") (pinfunction "3_3") (pintype "passive"))
      (node (ref "B1") (pin "A2") (pinfunction "A2_A2") (pintype "bidirectional"))
    )
    (net (code "10") (name "ADC4") (class "Default")
      (node (ref "ADC_RAIL") (pin "4") (pinfunction "4_4") (pintype "passive"))
      (node (ref "B1") (pin "A3") (pinfunction "A3_A3") (pintype "bidirectional"))
    )
    (net (code "11") (name "ADC5") (class "Default")
      (node (ref "ADC_RAIL") (pin "5") (pinfunction "5_5") (pintype "passive"))
      (node (ref "B1") (pin "A4") (pinfunction "A4_A4") (pintype "bidirectional"))
    )
    (net (code "12") (name "ADC6") (class "Default")
      (node (ref "ADC_RAIL") (pin "6") (pinfunction "6_6") (pintype "passive"))
      (node (ref "B1") (pin "A5") (pinfunction "A5_A5") (pintype "bidirectional"))
    )
    (net (code "13") (name "ADC7") (class "Default")
      (node (ref "ADC_RAIL") (pin "7") (pinfunction "7_7") (pintype "passive"))
      (node (ref "B1") (pin "A6") (pinfunction "A6_A6") (pintype "bidirectional"))
    )
    (net (code "14") (name "ADC8") (class "Default")
      (node (ref "ADC_RAIL") (pin "8") (pinfunction "8_8") (pintype "passive"))
      (node (ref "B1") (pin "A7") (pinfunction "A7_A7") (pintype "bidirectional"))
    )
    (net (code "15") (name "ADC9") (class "Default")
      (node (ref "ADC_RAIL") (pin "9") (pinfunction "9_9") (pintype "passive"))
      (node (ref "B1") (pin "A8") (pinfunction "A8_A8") (pintype "bidirectional"))
    )
    (net (code "16") (name "ADC10") (class "Default")
      (node (ref "ADC_RAIL") (pin "10") (pinfunction "10_10") (pintype "passive"))
      (node (ref "B1") (pin "A9") (pinfunction "A9_A9") (pintype "bidirectional"))
    )
    (net (code "17") (name "ADC11") (class "Default")
      (node (ref "ADC_RAIL") (pin "11") (pinfunction "11_11") (pintype "passive"))
      (node (ref "B1") (pin "A10") (pinfunction "A10_A10") (pintype "bidirectional"))
    )
    (net (code "18") (name "ADC12") (class "Default")
      (node (ref "ADC_RAIL") (pin "12") (pinfunction "12_12") (pintype "passive"))
      (node (ref "B1") (pin "A11") (pinfunction "A11_A11") (pintype "bidirectional"))
      (node (ref "RF_REC") (pin "3") (pinfunction "3_3") (pintype "passive"))
    )
    (net (code "19") (name "BUTTON1") (class "Default")
      (node (ref "B1") (pin "22") (pinfunction "22_22") (pintype "bidirectional"))
      (node (ref "R6") (pin "2") (pinfunction "2_2") (pintype "passive"))
      (node (ref "S1") (pin "3") (pinfunction "3_3") (pintype "passive"))
    )
    (net (code "20") (name "BUTTON2") (class "Default")
      (node (ref "B1") (pin "23") (pinfunction "23_23") (pintype "bidirectional"))
      (node (ref "R13") (pin "2") (pinfunction "2_2") (pintype "passive"))
      (node (ref "S5") (pin "3") (pinfunction "3_3") (pintype "passive"))
    )
    (net (code "21") (name "BUTTON3") (class "Default")
      (node (ref "B1") (pin "24") (pinfunction "24_24") (pintype "bidirectional"))
      (node (ref "R7") (pin "2") (pinfunction "2_2") (pintype "passive"))
      (node (ref "S2") (pin "3") (pinfunction "3_3") (pintype "passive"))
    )
    (net (code "22") (name "BUTTON4") (class "Default")
      (node (ref "B1") (pin "25") (pinfunction "25_25") (pintype "bidirectional"))
      (node (ref "R12") (pin "2") (pinfunction "2_2") (pintype "passive"))
      (node (ref "S4") (pin "3") (pinfunction "3_3") (pintype "passive"))
    )
    (net (code "23") (name "BUTTON5") (class "Default")
      (node (ref "B1") (pin "26") (pinfunction "26_26") (pintype "bidirectional"))
      (node (ref "R8") (pin "2") (pinfunction "2_2") (pintype "passive"))
      (node (ref "S3") (pin "3") (pinfunction "3_3") (pintype "passive"))
    )
    (net (code "24") (name "BUZZER") (class "Default")
      (node (ref "B1") (pin "44") (pinfunction "44_44") (pintype "bidirectional"))
      (node (ref "R34") (pin "1") (pinfunction "1_1") (pintype "passive"))
    )
    (net (code "25") (name "COM0") (class "Default")
      (node (ref "D4") (pin "A") (pinfunction "A_A") (pintype "passive"))
      (node (ref "LED1") (pin "16") (pinfunction "16_16") (pintype "bidirectional"))
      (node (ref "U2") (pin "P$2") (pinfunction "COM0/AD_P$2") (pintype "bidirectional"))
    )
    (net (code "26") (name "COM1") (class "Default")
      (node (ref "LED1") (pin "11") (pinfunction "11_11") (pintype "bidirectional"))
      (node (ref "U2") (pin "P$3") (pinfunction "COM1/KS0_P$3") (pintype "bidirectional"))
    )
    (net (code "27") (name "COM2") (class "Default")
      (node (ref "LED2") (pin "16") (pinfunction "16_16") (pintype "bidirectional"))
      (node (ref "U2") (pin "P$4") (pinfunction "COM2/KS1_P$4") (pintype "bidirectional"))
    )
    (net (code "28") (name "COM3") (class "Default")
      (node (ref "LED2") (pin "11") (pinfunction "11_11") (pintype "bidirectional"))
      (node (ref "U2") (pin "P$5") (pinfunction "COM3/KS2_P$5") (pintype "bidirectional"))
    )
    (net (code "29") (name "GND") (class "Default")
      (node (ref "24VIN") (pin "GND") (pinfunction "GND_GND") (pintype "power_in"))
      (node (ref "24VIN") (pin "GNDBREAK") (pinfunction "GNDBREAK_GNDBREAK") (pintype "power_in"))
      (node (ref "B1") (pin "GND@0") (pinfunction "GND_GND@0") (pintype "bidirectional"))
      (node (ref "B1") (pin "GND@1") (pinfunction "GND_GND@1") (pintype "bidirectional"))
      (node (ref "B1") (pin "GND@2") (pinfunction "GND_GND@2") (pintype "bidirectional"))
      (node (ref "B1") (pin "GND@3") (pinfunction "GND_GND@3") (pintype "bidirectional"))
      (node (ref "B1") (pin "GND@4") (pinfunction "GND_GND@4") (pintype "bidirectional"))
      (node (ref "BLE") (pin "2") (pinfunction "2_2") (pintype "passive"))
      (node (ref "BLE") (pin "7") (pinfunction "7_7") (pintype "passive"))
      (node (ref "BT") (pin "4") (pinfunction "4_4") (pintype "passive"))
      (node (ref "C1") (pin "1") (pinfunction "1_1") (pintype "passive"))
      (node (ref "C10") (pin "1") (pinfunction "1_1") (pintype "passive"))
      (node (ref "C11") (pin "2") (pinfunction "2_2") (pintype "passive"))
      (node (ref "C12") (pin "1") (pinfunction "1_1") (pintype "passive"))
      (node (ref "C13") (pin "2") (pinfunction "2_2") (pintype "passive"))
      (node (ref "C14") (pin "1") (pinfunction "1_1") (pintype "passive"))
      (node (ref "C15") (pin "-") (pinfunction "-_-") (pintype "passive"))
      (node (ref "C16") (pin "-") (pinfunction "-_-") (pintype "passive"))
      (node (ref "C17") (pin "-") (pinfunction "-_-") (pintype "passive"))
      (node (ref "C18") (pin "1") (pinfunction "1_1") (pintype "passive"))
      (node (ref "C2") (pin "2") (pinfunction "2_2") (pintype "passive"))
      (node (ref "C20") (pin "-") (pinfunction "-_-") (pintype "passive"))
      (node (ref "C21") (pin "-") (pinfunction "-_-") (pintype "passive"))
      (node (ref "C3") (pin "1") (pinfunction "1_1") (pintype "passive"))
      (node (ref "C4") (pin "2") (pinfunction "2_2") (pintype "passive"))
      (node (ref "C5") (pin "1") (pinfunction "1_1") (pintype "passive"))
      (node (ref "C6") (pin "2") (pinfunction "2_2") (pintype "passive"))
      (node (ref "C7") (pin "2") (pinfunction "2_2") (pintype "passive"))
      (node (ref "C8") (pin "1") (pinfunction "1_1") (pintype "passive"))
      (node (ref "C9") (pin "2") (pinfunction "2_2") (pintype "passive"))
      (node (ref "D10") (pin "A") (pinfunction "A_A") (pintype "passive"))
      (node (ref "D11") (pin "A") (pinfunction "A_A") (pintype "passive"))
      (node (ref "D12") (pin "A") (pinfunction "A_A") (pintype "passive"))
      (node (ref "D17") (pin "A") (pinfunction "A_A") (pintype "passive"))
      (node (ref "D18") (pin "A") (pinfunction "A_A") (pintype "passive"))
      (node (ref "D19") (pin "A") (pinfunction "A_A") (pintype "passive"))
      (node (ref "D20") (pin "A") (pinfunction "A_A") (pintype "passive"))
      (node (ref "D22") (pin "A") (pinfunction "A_A") (pintype "passive"))
      (node (ref "D9") (pin "A") (pinfunction "A_A") (pintype "passive"))
      (node (ref "GND_RAIL1") (pin "1") (pinfunction "1_1") (pintype "passive"))
      (node (ref "GND_RAIL1") (pin "10") (pinfunction "10_10") (pintype "passive"))
      (node (ref "GND_RAIL1") (pin "11") (pinfunction "11_11") (pintype "passive"))
      (node (ref "GND_RAIL1") (pin "12") (pinfunction "12_12") (pintype "passive"))
      (node (ref "GND_RAIL1") (pin "2") (pinfunction "2_2") (pintype "passive"))
      (node (ref "GND_RAIL1") (pin "3") (pinfunction "3_3") (pintype "passive"))
      (node (ref "GND_RAIL1") (pin "4") (pinfunction "4_4") (pintype "passive"))
      (node (ref "GND_RAIL1") (pin "5") (pinfunction "5_5") (pintype "passive"))
      (node (ref "GND_RAIL1") (pin "6") (pinfunction "6_6") (pintype "passive"))
      (node (ref "GND_RAIL1") (pin "7") (pinfunction "7_7") (pintype "passive"))
      (node (ref "GND_RAIL1") (pin "8") (pinfunction "8_8") (pintype "passive"))
      (node (ref "GND_RAIL1") (pin "9") (pinfunction "9_9") (pintype "passive"))
      (node (ref "GND_RAIL2") (pin "1") (pinfunction "1_1") (pintype "passive"))
      (node (ref "GND_RAIL2") (pin "10") (pinfunction "10_10") (pintype "passive"))
      (node (ref "GND_RAIL2") (pin "11") (pinfunction "11_11") (pintype "passive"))
      (node (ref "GND_RAIL2") (pin "12") (pinfunction "12_12") (pintype "passive"))
      (node (ref "GND_RAIL2") (pin "2") (pinfunction "2_2") (pintype "passive"))
      (node (ref "GND_RAIL2") (pin "3") (pinfunction "3_3") (pintype "passive"))
      (node (ref "GND_RAIL2") (pin "4") (pinfunction "4_4") (pintype "passive"))
      (node (ref "GND_RAIL2") (pin "5") (pinfunction "5_5") (pintype "passive"))
      (node (ref "GND_RAIL2") (pin "6") (pinfunction "6_6") (pintype "passive"))
      (node (ref "GND_RAIL2") (pin "7") (pinfunction "7_7") (pintype "passive"))
      (node (ref "GND_RAIL2") (pin "8") (pinfunction "8_8") (pintype "passive"))
      (node (ref "GND_RAIL2") (pin "9") (pinfunction "9_9") (pintype "passive"))
      (node (ref "GND_RAIL3") (pin "1") (pinfunction "1_1") (pintype "passive"))
      (node (ref "GND_RAIL3") (pin "2") (pinfunction "2_2") (pintype "passive"))
      (node (ref "GPS") (pin "2") (pinfunction "2_2") (pintype "passive"))
      (node (ref "IC1") (pin "1") (pinfunction "SEN_A_1") (pintype "input"))
      (node (ref "IC1") (pin "15") (pinfunction "SEN_B_15") (pintype "input"))
      (node (ref "IC1") (pin "8") (pinfunction "GND_8") (pintype "power_in"))
      (node (ref "IC2") (pin "1") (pinfunction "SEN_A_1") (pintype "input"))
      (node (ref "IC2") (pin "15") (pinfunction "SEN_B_15") (pintype "input"))
      (node (ref "IC2") (pin "8") (pinfunction "GND_8") (pintype "power_in"))
      (node (ref "IC3") (pin "4") (pinfunction "GND_4") (pintype "power_in"))
      (node (ref "IMU") (pin "4") (pinfunction "4_4") (pintype "passive"))
      (node (ref "J5") (pin "1") (pinfunction "1_1") (pintype "passive"))
      (node (ref "J5") (pin "2") (pinfunction "2_2") (pintype "passive"))
      (node (ref "J5") (pin "3") (pinfunction "3_3") (pintype "passive"))
      (node (ref "J5") (pin "4") (pinfunction "4_4") (pintype "passive"))
      (node (ref "J5") (pin "5") (pinfunction "5_5") (pintype "passive"))
      (node (ref "J5") (pin "6") (pinfunction "6_6") (pintype "passive"))
      (node (ref "J5") (pin "7") (pinfunction "7_7") (pintype "passive"))
      (node (ref "J5") (pin "8") (pinfunction "8_8") (pintype "passive"))
      (node (ref "J6") (pin "1") (pinfunction "1_1") (pintype "passive"))
      (node (ref "J6") (pin "2") (pinfunction "2_2") (pintype "passive"))
      (node (ref "J6") (pin "3") (pinfunction "3_3") (pintype "passive"))
      (node (ref "J6") (pin "4") (pinfunction "4_4") (pintype "passive"))
      (node (ref "J6") (pin "5") (pinfunction "5_5") (pintype "passive"))
      (node (ref "J6") (pin "6") (pinfunction "6_6") (pintype "passive"))
      (node (ref "J6") (pin "7") (pinfunction "7_7") (pintype "passive"))
      (node (ref "J6") (pin "8") (pinfunction "8_8") (pintype "passive"))
      (node (ref "J7") (pin "1") (pinfunction "1_1") (pintype "passive"))
      (node (ref "J7") (pin "2") (pinfunction "2_2") (pintype "passive"))
      (node (ref "J7") (pin "3") (pinfunction "3_3") (pintype "passive"))
      (node (ref "J7") (pin "4") (pinfunction "4_4") (pintype "passive"))
      (node (ref "J7") (pin "5") (pinfunction "5_5") (pintype "passive"))
      (node (ref "J7") (pin "6") (pinfunction "6_6") (pintype "passive"))
      (node (ref "J7") (pin "7") (pinfunction "7_7") (pintype "passive"))
      (node (ref "J7") (pin "8") (pinfunction "8_8") (pintype "passive"))
      (node (ref "MC1_VS") (pin "P2") (pinfunction "2_P2") (pintype "passive"))
      (node (ref "R11") (pin "1") (pinfunction "1_1") (pintype "passive"))
      (node (ref "R12") (pin "1") (pinfunction "1_1") (pintype "passive"))
      (node (ref "R13") (pin "1") (pinfunction "1_1") (pintype "passive"))
      (node (ref "R14") (pin "1") (pinfunction "1_1") (pintype "passive"))
      (node (ref "R17") (pin "1") (pinfunction "1_1") (pintype "passive"))
      (node (ref "R18") (pin "1") (pinfunction "1_1") (pintype "passive"))
      (node (ref "R19") (pin "1") (pinfunction "1_1") (pintype "passive"))
      (node (ref "R20") (pin "1") (pinfunction "1_1") (pintype "passive"))
      (node (ref "R21") (pin "1") (pinfunction "1_1") (pintype "passive"))
      (node (ref "R22") (pin "1") (pinfunction "1_1") (pintype "passive"))
      (node (ref "R31") (pin "1") (pinfunction "1_1") (pintype "passive"))
      (node (ref "R6") (pin "1") (pinfunction "1_1") (pintype "passive"))
      (node (ref "R7") (pin "1") (pinfunction "1_1") (pintype "passive"))
      (node (ref "R8") (pin "1") (pinfunction "1_1") (pintype "passive"))
      (node (ref "RF_REC") (pin "1") (pinfunction "1_1") (pintype "passive"))
      (node (ref "RF_TRANS") (pin "3") (pinfunction "3_3") (pintype "passive"))
      (node (ref "SG2") (pin "+") (pinfunction "1_+") (pintype "passive"))
      (node (ref "U$12") (pin "P$3") (pinfunction "A_P$3") (pintype "passive"))
      (node (ref "U$14") (pin "P$3") (pinfunction "A_P$3") (pintype "passive"))
      (node (ref "U1") (pin "H3") (pinfunction "H-_H3") (pintype "bidirectional"))
      (node (ref "U1") (pin "V3") (pinfunction "V-_V3") (pintype "bidirectional"))
      (node (ref "U2") (pin "P$1") (pinfunction "VSS_P$1") (pintype "bidirectional"))
      (node (ref "U3") (pin "2") (pinfunction "GND_2") (pintype "power_in"))
      (node (ref "U5") (pin "2") (pinfunction "GND_2") (pintype "power_in"))
      (node (ref "VR1") (pin "P$3") (pinfunction "A_P$3") (pintype "passive"))
      (node (ref "WIFI") (pin "2") (pinfunction "2_2") (pintype "passive"))
      (node (ref "X1") (pin "1") (pinfunction "VSS_1") (pintype "power_in"))
      (node (ref "X1") (pin "16") (pinfunction "K_16") (pintype "input"))
      (node (ref "X1") (pin "5") (pinfunction "RW_5") (pintype "input"))
      (node (ref "XBEE") (pin "10") (pinfunction "GND_10") (pintype "power_in"))
    )
    (net (code "30") (name "HDW_RX0") (class "Default")
      (node (ref "B1") (pin "0") (pinfunction "0(RX0)_0") (pintype "bidirectional"))
      (node (ref "HDW_RX") (pin "1") (pinfunction "1_1") (pintype "passive"))
      (node (ref "XBEE") (pin "2") (pinfunction "DOUT_2") (pintype "output"))
    )
    (net (code "31") (name "HDW_RX1") (class "Default")
      (node (ref "B1") (pin "19") (pinfunction "19(RX1)_19") (pintype "bidirectional"))
      (node (ref "HDW_RX") (pin "2") (pinfunction "2_2") (pintype "passive"))
      (node (ref "WIFI") (pin "8") (pinfunction "8_8") (pintype "passive"))
    )
    (net (code "32") (name "HDW_RX2") (class "Default")
      (node (ref "B1") (pin "17") (pinfunction "17(RX2)_17") (pintype "bidirectional"))
      (node (ref "BLE") (pin "6") (pinfunction "6_6") (pintype "passive"))
      (node (ref "BT") (pin "3") (pinfunction "3_3") (pintype "passive"))
      (node (ref "HDW_RX") (pin "3") (pinfunction "3_3") (pintype "passive"))
    )
    (net (code "33") (name "HDW_RX3") (class "Default")
      (node (ref "B1") (pin "15") (pinfunction "15(RX3)_15") (pintype "bidirectional"))
      (node (ref "GPS") (pin "4") (pinfunction "4_4") (pintype "passive"))
      (node (ref "HDW_RX") (pin "4") (pinfunction "4_4") (pintype "passive"))
    )
    (net (code "34") (name "HDW_TX0") (class "Default")
      (node (ref "B1") (pin "1") (pinfunction "1(TX0)_1") (pintype "bidirectional"))
      (node (ref "HDW_TX") (pin "1") (pinfunction "1_1") (pintype "passive"))
      (node (ref "XBEE") (pin "3") (pinfunction "DIN_3") (pintype "input"))
    )
    (net (code "35") (name "HDW_TX1") (class "Default")
      (node (ref "B1") (pin "18") (pinfunction "18(TX1)_18") (pintype "bidirectional"))
      (node (ref "HDW_TX") (pin "2") (pinfunction "2_2") (pintype "passive"))
      (node (ref "WIFI") (pin "1") (pinfunction "1_1") (pintype "passive"))
    )
    (net (code "36") (name "HDW_TX2") (class "Default")
      (node (ref "B1") (pin "16") (pinfunction "16(TX2)_16") (pintype "bidirectional"))
      (node (ref "BLE") (pin "5") (pinfunction "5_5") (pintype "passive"))
      (node (ref "BT") (pin "2") (pinfunction "2_2") (pintype "passive"))
      (node (ref "HDW_TX") (pin "3") (pinfunction "3_3") (pintype "passive"))
    )
    (net (code "37") (name "HDW_TX3") (class "Default")
      (node (ref "B1") (pin "14") (pinfunction "14(TX3)_14") (pintype "bidirectional"))
      (node (ref "GPS") (pin "3") (pinfunction "3_3") (pintype "passive"))
      (node (ref "HDW_TX") (pin "4") (pinfunction "4_4") (pintype "passive"))
    )
    (net (code "38") (name "JOYSTICK_BUTTON") (class "Default")
      (node (ref "B1") (pin "27") (pinfunction "27_27") (pintype "bidirectional"))
      (node (ref "R31") (pin "2") (pinfunction "2_2") (pintype "passive"))
      (node (ref "U1") (pin "B2A") (pinfunction "SEL-_B2A") (pintype "bidirectional"))
    )
    (net (code "39") (name "JOYSTICK_X") (class "Default")
      (node (ref "B1") (pin "A14") (pinfunction "A14_A14") (pintype "bidirectional"))
      (node (ref "U1") (pin "H2") (pinfunction "H_H2") (pintype "bidirectional"))
    )
    (net (code "40") (name "JOYSTICK_Y") (class "Default")
      (node (ref "B1") (pin "A15") (pinfunction "A15_A15") (pintype "bidirectional"))
      (node (ref "U1") (pin "V2") (pinfunction "V_V2") (pintype "bidirectional"))
    )
    (net (code "41") (name "LCD_D0") (class "Default")
      (node (ref "B1") (pin "30") (pinfunction "30_30") (pintype "bidirectional"))
      (node (ref "X1") (pin "7") (pinfunction "DB0_7") (pintype "bidirectional"))
    )
    (net (code "42") (name "LCD_D1") (class "Default")
      (node (ref "B1") (pin "31") (pinfunction "31_31") (pintype "bidirectional"))
      (node (ref "X1") (pin "8") (pinfunction "DB1_8") (pintype "bidirectional"))
    )
    (net (code "43") (name "LCD_D2") (class "Default")
      (node (ref "B1") (pin "32") (pinfunction "32_32") (pintype "bidirectional"))
      (node (ref "X1") (pin "9") (pinfunction "DB2_9") (pintype "bidirectional"))
    )
    (net (code "44") (name "LCD_D3") (class "Default")
      (node (ref "B1") (pin "33") (pinfunction "33_33") (pintype "bidirectional"))
      (node (ref "X1") (pin "10") (pinfunction "DB3_10") (pintype "bidirectional"))
    )
    (net (code "45") (name "LCD_D4") (class "Default")
      (node (ref "B1") (pin "34") (pinfunction "34_34") (pintype "bidirectional"))
      (node (ref "X1") (pin "11") (pinfunction "DB4_11") (pintype "bidirectional"))
    )
    (net (code "46") (name "LCD_D5") (class "Default")
      (node (ref "B1") (pin "35") (pinfunction "35_35") (pintype "bidirectional"))
      (node (ref "X1") (pin "12") (pinfunction "DB5_12") (pintype "bidirectional"))
    )
    (net (code "47") (name "LCD_D6") (class "Default")
      (node (ref "B1") (pin "36") (pinfunction "36_36") (pintype "bidirectional"))
      (node (ref "X1") (pin "13") (pinfunction "DB6_13") (pintype "bidirectional"))
    )
    (net (code "48") (name "LCD_D7") (class "Default")
      (node (ref "B1") (pin "37") (pinfunction "37_37") (pintype "bidirectional"))
      (node (ref "X1") (pin "14") (pinfunction "DB7_14") (pintype "bidirectional"))
    )
    (net (code "49") (name "LCD_E") (class "Default")
      (node (ref "B1") (pin "29") (pinfunction "29_29") (pintype "bidirectional"))
      (node (ref "X1") (pin "6") (pinfunction "E_6") (pintype "input"))
    )
    (net (code "50") (name "LCD_RS") (class "Default")
      (node (ref "B1") (pin "28") (pinfunction "28_28") (pintype "bidirectional"))
      (node (ref "X1") (pin "4") (pinfunction "RS_4") (pintype "input"))
    )
    (net (code "51") (name "MCONTROLR1_INP1") (class "Default")
      (node (ref "B1") (pin "39") (pinfunction "39_39") (pintype "bidirectional"))
      (node (ref "IC2") (pin "5") (pinfunction "INPUT1_5") (pintype "input"))
    )
    (net (code "52") (name "MCONTROLR1_INP2") (class "Default")
      (node (ref "B1") (pin "40") (pinfunction "40_40") (pintype "bidirectional"))
      (node (ref "IC2") (pin "7") (pinfunction "INPUT2_7") (pintype "input"))
    )
    (net (code "53") (name "MCONTROLR1_INP3") (class "Default")
      (node (ref "B1") (pin "41") (pinfunction "41_41") (pintype "bidirectional"))
      (node (ref "IC2") (pin "10") (pinfunction "INPUT3_10") (pintype "input"))
    )
    (net (code "54") (name "MCONTROLR1_INP4") (class "Default")
      (node (ref "B1") (pin "42") (pinfunction "42_42") (pintype "bidirectional"))
      (node (ref "IC2") (pin "12") (pinfunction "INPUT4_12") (pintype "input"))
    )
    (net (code "55") (name "MCONTROLR2_INP1") (class "Default")
      (node (ref "B1") (pin "43") (pinfunction "43_43") (pintype "bidirectional"))
      (node (ref "IC1") (pin "5") (pinfunction "INPUT1_5") (pintype "input"))
    )
    (net (code "56") (name "MCONTROLR2_INP2") (class "Default")
      (node (ref "B1") (pin "45") (pinfunction "45_45") (pintype "bidirectional"))
      (node (ref "IC1") (pin "7") (pinfunction "INPUT2_7") (pintype "input"))
    )
    (net (code "57") (name "MCONTROLR2_INP3") (class "Default")
      (node (ref "B1") (pin "46") (pinfunction "46_46") (pintype "bidirectional"))
      (node (ref "IC1") (pin "10") (pinfunction "INPUT3_10") (pintype "input"))
    )
    (net (code "58") (name "MCONTROLR2_INP4") (class "Default")
      (node (ref "B1") (pin "47") (pinfunction "47_47") (pintype "bidirectional"))
      (node (ref "IC1") (pin "12") (pinfunction "INPUT4_12") (pintype "input"))
    )
    (net (code "59") (name "N$41") (class "Default")
      (node (ref "R11") (pin "2") (pinfunction "2_2") (pintype "passive"))
      (node (ref "U3") (pin "6") (pinfunction "A0_6") (pintype "input"))
    )
    (net (code "60") (name "Net-(A0-Pad1)") (class "Default")
      (node (ref "A0") (pin "1") (pinfunction "1_1") (pintype "passive"))
      (node (ref "R4") (pin "2") (pinfunction "2_2") (pintype "passive"))
    )
    (net (code "61") (name "Net-(A1-Pad1)") (class "Default")
      (node (ref "A1") (pin "1") (pinfunction "1_1") (pintype "passive"))
      (node (ref "R3") (pin "2") (pinfunction "2_2") (pintype "passive"))
    )
    (net (code "62") (name "Net-(A2-Pad1)") (class "Default")
      (node (ref "A2") (pin "1") (pinfunction "1_1") (pintype "passive"))
      (node (ref "R5") (pin "2") (pinfunction "2_2") (pintype "passive"))
    )
    (net (code "63") (name "Net-(D4-PadC)") (class "Default")
      (node (ref "D4") (pin "C") (pinfunction "C_C") (pintype "passive"))
      (node (ref "R3") (pin "1") (pinfunction "1_1") (pintype "passive"))
      (node (ref "R4") (pin "1") (pinfunction "1_1") (pintype "passive"))
      (node (ref "R5") (pin "1") (pinfunction "1_1") (pintype "passive"))
    )
    (net (code "64") (name "Net-(D21-A)") (class "Default")
      (node (ref "B1") (pin "3.3V") (pinfunction "3.3V_3.3V") (pintype "bidirectional"))
      (node (ref "D21") (pin "1") (pinfunction "A_1") (pintype "passive"))
    )
    (net (code "65") (name "Net-(IC1-OUT1)") (class "Default")
      (node (ref "D13") (pin "A") (pinfunction "A_A") (pintype "passive"))
      (node (ref "D17") (pin "C") (pinfunction "C_C") (pintype "passive"))
      (node (ref "IC1") (pin "2") (pinfunction "OUT1_2") (pintype "output"))
      (node (ref "MC2_MOTORA") (pin "P1") (pinfunction "1_P1") (pintype "passive"))
    )
    (net (code "66") (name "Net-(IC1-OUT2)") (class "Default")
      (node (ref "D14") (pin "A") (pinfunction "A_A") (pintype "passive"))
      (node (ref "D18") (pin "C") (pinfunction "C_C") (pintype "passive"))
      (node (ref "IC1") (pin "3") (pinfunction "OUT2_3") (pintype "output"))
      (node (ref "MC2_MOTORA") (pin "P2") (pinfunction "2_P2") (pintype "passive"))
    )
    (net (code "67") (name "Net-(IC1-OUT3)") (class "Default")
      (node (ref "D15") (pin "A") (pinfunction "A_A") (pintype "passive"))
      (node (ref "D19") (pin "C") (pinfunction "C_C") (pintype "passive"))
      (node (ref "IC1") (pin "13") (pinfunction "OUT3_13") (pintype "output"))
      (node (ref "MC2_MOTORB") (pin "P1") (pinfunction "1_P1") (pintype "passive"))
    )
    (net (code "68") (name "Net-(IC1-OUT4)") (class "Default")
      (node (ref "D16") (pin "A") (pinfunction "A_A") (pintype "passive"))
      (node (ref "D20") (pin "C") (pinfunction "C_C") (pintype "passive"))
      (node (ref "IC1") (pin "14") (pinfunction "OUT4_14") (pintype "output"))
      (node (ref "MC2_MOTORB") (pin "P2") (pinfunction "2_P2") (pintype "passive"))
    )
    (net (code "69") (name "Net-(IC1-VS)") (class "Default")
      (node (ref "C4") (pin "1") (pinfunction "1_1") (pintype "passive"))
      (node (ref "C7") (pin "1") (pinfunction "1_1") (pintype "passive"))
      (node (ref "D13") (pin "C") (pinfunction "C_C") (pintype "passive"))
      (node (ref "D14") (pin "C") (pinfunction "C_C") (pintype "passive"))
      (node (ref "D15") (pin "C") (pinfunction "C_C") (pintype "passive"))
      (node (ref "D16") (pin "C") (pinfunction "C_C") (pintype "passive"))
      (node (ref "D5") (pin "C") (pinfunction "C_C") (pintype "passive"))
      (node (ref "D6") (pin "C") (pinfunction "C_C") (pintype "passive"))
      (node (ref "D7") (pin "C") (pinfunction "C_C") (pintype "passive"))
      (node (ref "D8") (pin "C") (pinfunction "C_C") (pintype "passive"))
      (node (ref "IC1") (pin "4") (pinfunction "VS_4") (pintype "power_in"))
      (node (ref "IC2") (pin "4") (pinfunction "VS_4") (pintype "power_in"))
      (node (ref "MC1_VS") (pin "P1") (pinfunction "1_P1") (pintype "passive"))
    )
    (net (code "70") (name "Net-(IC2-OUT1)") (class "Default")
      (node (ref "D5") (pin "A") (pinfunction "A_A") (pintype "passive"))
      (node (ref "D9") (pin "C") (pinfunction "C_C") (pintype "passive"))
      (node (ref "IC2") (pin "2") (pinfunction "OUT1_2") (pintype "output"))
      (node (ref "MC1_MOTORA") (pin "P1") (pinfunction "1_P1") (pintype "passive"))
    )
    (net (code "71") (name "Net-(IC2-OUT2)") (class "Default")
      (node (ref "D10") (pin "C") (pinfunction "C_C") (pintype "passive"))
      (node (ref "D6") (pin "A") (pinfunction "A_A") (pintype "passive"))
      (node (ref "IC2") (pin "3") (pinfunction "OUT2_3") (pintype "output"))
      (node (ref "MC1_MOTORA") (pin "P2") (pinfunction "2_P2") (pintype "passive"))
    )
    (net (code "72") (name "Net-(IC2-OUT3)") (class "Default")
      (node (ref "D11") (pin "C") (pinfunction "C_C") (pintype "passive"))
      (node (ref "D7") (pin "A") (pinfunction "A_A") (pintype "passive"))
      (node (ref "IC2") (pin "13") (pinfunction "OUT3_13") (pintype "output"))
      (node (ref "MC1_MOTORB") (pin "P1") (pinfunction "1_P1") (pintype "passive"))
    )
    (net (code "73") (name "Net-(IC2-OUT4)") (class "Default")
      (node (ref "D12") (pin "C") (pinfunction "C_C") (pintype "passive"))
      (node (ref "D8") (pin "A") (pinfunction "A_A") (pintype "passive"))
      (node (ref "IC2") (pin "14") (pinfunction "OUT4_14") (pintype "output"))
      (node (ref "MC1_MOTORB") (pin "P2") (pinfunction "2_P2") (pintype "passive"))
    )
    (net (code "74") (name "Net-(IC3-FB)") (class "Default")
      (node (ref "C19") (pin "2") (pinfunction "2_2") (pintype "passive"))
      (node (ref "IC3") (pin "6") (pinfunction "FB_6") (pintype "input"))
    )
    (net (code "75") (name "Net-(IC3-VIN)") (class "Default")
      (node (ref "24VIN") (pin "PWR") (pinfunction "PWR_PWR") (pintype "power_in"))
      (node (ref "C15") (pin "+") (pinfunction "+_+") (pintype "passive"))
      (node (ref "C16") (pin "+") (pinfunction "+_+") (pintype "passive"))
      (node (ref "C17") (pin "+") (pinfunction "+_+") (pintype "passive"))
      (node (ref "C18") (pin "2") (pinfunction "2_2") (pintype "passive"))
      (node (ref "IC3") (pin "2") (pinfunction "VIN_2") (pintype "power_in"))
    )
    (net (code "76") (name "Net-(IC3-VSW)") (class "Default")
      (node (ref "C19") (pin "1") (pinfunction "1_1") (pintype "passive"))
      (node (ref "D22") (pin "C") (pinfunction "C_C") (pintype "passive"))
      (node (ref "IC3") (pin "1") (pinfunction "VSW_1") (pintype "output"))
      (node (ref "L1") (pin "1") (pinfunction "1_1") (pintype "passive"))
    )
    (net (code "77") (name "Net-(R14-Pad2)") (class "Default")
      (node (ref "R14") (pin "2") (pinfunction "2_2") (pintype "passive"))
      (node (ref "S15") (pin "O") (pinfunction "O_O") (pintype "passive"))
    )
    (net (code "78") (name "Net-(R18-Pad2)") (class "Default")
      (node (ref "R18") (pin "2") (pinfunction "2_2") (pintype "passive"))
      (node (ref "S6") (pin "O") (pinfunction "O_O") (pintype "passive"))
    )
    (net (code "79") (name "Net-(R19-Pad2)") (class "Default")
      (node (ref "R19") (pin "2") (pinfunction "2_2") (pintype "passive"))
      (node (ref "S7") (pin "O") (pinfunction "O_O") (pintype "passive"))
    )
    (net (code "80") (name "Net-(R20-Pad2)") (class "Default")
      (node (ref "R20") (pin "2") (pinfunction "2_2") (pintype "passive"))
      (node (ref "S8") (pin "O") (pinfunction "O_O") (pintype "passive"))
    )
    (net (code "81") (name "Net-(R21-Pad2)") (class "Default")
      (node (ref "R21") (pin "2") (pinfunction "2_2") (pintype "passive"))
      (node (ref "S9") (pin "O") (pinfunction "O_O") (pintype "passive"))
    )
    (net (code "82") (name "Net-(R22-Pad2)") (class "Default")
      (node (ref "R22") (pin "2") (pinfunction "2_2") (pintype "passive"))
      (node (ref "S10") (pin "O") (pinfunction "O_O") (pintype "passive"))
    )
    (net (code "83") (name "Net-(R23-Pad1)") (class "Default")
      (node (ref "R23") (pin "1") (pinfunction "1_1") (pintype "passive"))
      (node (ref "WIFI") (pin "5") (pinfunction "5_5") (pintype "passive"))
    )
    (net (code "84") (name "Net-(R24-Pad1)") (class "Default")
      (node (ref "R24") (pin "1") (pinfunction "1_1") (pintype "passive"))
      (node (ref "WIFI") (pin "6") (pinfunction "6_6") (pintype "passive"))
    )
    (net (code "85") (name "Net-(SG2-2)") (class "Default")
      (node (ref "R34") (pin "2") (pinfunction "2_2") (pintype "passive"))
      (node (ref "SG2") (pin "-") (pinfunction "2_-") (pintype "passive"))
    )
    (net (code "86") (name "Net-(U$12-S)") (class "Default")
      (node (ref "B1") (pin "A13") (pinfunction "A13_A13") (pintype "bidirectional"))
      (node (ref "U$12") (pin "P$2") (pinfunction "S_P$2") (pintype "passive"))
    )
    (net (code "87") (name "Net-(U$14-S)") (class "Default")
      (node (ref "B1") (pin "A12") (pinfunction "A12_A12") (pintype "bidirectional"))
      (node (ref "U$14") (pin "P$2") (pinfunction "S_P$2") (pintype "passive"))
    )
    (net (code "88") (name "Net-(U2-ROW3{slash}K1)") (class "Default")
      (node (ref "LED1") (pin "7") (pinfunction "7_7") (pintype "bidirectional"))
      (node (ref "LED2") (pin "7") (pinfunction "7_7") (pintype "bidirectional"))
      (node (ref "U2") (pin "P$22") (pinfunction "ROW3/K1_P$22") (pintype "bidirectional"))
    )
    (net (code "89") (name "Net-(U2-ROW4{slash}K2)") (class "Default")
      (node (ref "LED1") (pin "1") (pinfunction "1_1") (pintype "bidirectional"))
      (node (ref "LED2") (pin "1") (pinfunction "1_1") (pintype "bidirectional"))
      (node (ref "U2") (pin "P$21") (pinfunction "ROW4/K2_P$21") (pintype "bidirectional"))
    )
    (net (code "90") (name "Net-(U2-ROW5{slash}K3)") (class "Default")
      (node (ref "LED1") (pin "18") (pinfunction "18_18") (pintype "bidirectional"))
      (node (ref "LED2") (pin "18") (pinfunction "18_18") (pintype "bidirectional"))
      (node (ref "U2") (pin "P$20") (pinfunction "ROW5/K3_P$20") (pintype "bidirectional"))
    )
    (net (code "91") (name "Net-(U2-ROW6{slash}K4)") (class "Default")
      (node (ref "LED1") (pin "13") (pinfunction "13_13") (pintype "bidirectional"))
      (node (ref "LED2") (pin "13") (pinfunction "13_13") (pintype "bidirectional"))
      (node (ref "U2") (pin "P$19") (pinfunction "ROW6/K4_P$19") (pintype "bidirectional"))
    )
    (net (code "92") (name "Net-(U2-ROW7{slash}K5)") (class "Default")
      (node (ref "LED1") (pin "6") (pinfunction "6_6") (pintype "bidirectional"))
      (node (ref "LED2") (pin "6") (pinfunction "6_6") (pintype "bidirectional"))
      (node (ref "U2") (pin "P$18") (pinfunction "ROW7/K5_P$18") (pintype "bidirectional"))
    )
    (net (code "93") (name "Net-(U2-ROW8{slash}K6)") (class "Default")
      (node (ref "LED1") (pin "17") (pinfunction "17_17") (pintype "bidirectional"))
      (node (ref "LED2") (pin "17") (pinfunction "17_17") (pintype "bidirectional"))
      (node (ref "U2") (pin "P$17") (pinfunction "ROW8/K6_P$17") (pintype "bidirectional"))
    )
    (net (code "94") (name "Net-(U2-ROW9{slash}K7)") (class "Default")
      (node (ref "LED1") (pin "15") (pinfunction "15_15") (pintype "bidirectional"))
      (node (ref "LED2") (pin "15") (pinfunction "15_15") (pintype "bidirectional"))
      (node (ref "U2") (pin "P$16") (pinfunction "ROW9/K7_P$16") (pintype "bidirectional"))
    )
    (net (code "95") (name "Net-(U2-ROW10{slash}K8)") (class "Default")
      (node (ref "LED1") (pin "14") (pinfunction "14_14") (pintype "bidirectional"))
      (node (ref "LED2") (pin "14") (pinfunction "14_14") (pintype "bidirectional"))
      (node (ref "U2") (pin "P$15") (pinfunction "ROW10/K8_P$15") (pintype "bidirectional"))
    )
    (net (code "96") (name "Net-(U2-ROW11{slash}K9)") (class "Default")
      (node (ref "LED1") (pin "2") (pinfunction "2_2") (pintype "bidirectional"))
      (node (ref "LED2") (pin "2") (pinfunction "2_2") (pintype "bidirectional"))
      (node (ref "U2") (pin "P$14") (pinfunction "ROW11/K9_P$14") (pintype "bidirectional"))
    )
    (net (code "97") (name "Net-(U2-ROW12{slash}K10)") (class "Default")
      (node (ref "LED1") (pin "4") (pinfunction "4_4") (pintype "bidirectional"))
      (node (ref "LED2") (pin "4") (pinfunction "4_4") (pintype "bidirectional"))
      (node (ref "U2") (pin "P$13") (pinfunction "ROW12/K10_P$13") (pintype "bidirectional"))
    )
    (net (code "98") (name "Net-(U2-ROW13{slash}K11)") (class "Default")
      (node (ref "LED1") (pin "5") (pinfunction "5_5") (pintype "bidirectional"))
      (node (ref "LED2") (pin "5") (pinfunction "5_5") (pintype "bidirectional"))
      (node (ref "U2") (pin "P$12") (pinfunction "ROW13/K11_P$12") (pintype "bidirectional"))
    )
    (net (code "99") (name "Net-(U2-ROW14{slash}K12)") (class "Default")
      (node (ref "LED1") (pin "8") (pinfunction "8_8") (pintype "bidirectional"))
      (node (ref "LED2") (pin "8") (pinfunction "8_8") (pintype "bidirectional"))
      (node (ref "U2") (pin "P$11") (pinfunction "ROW14/K12_P$11") (pintype "bidirectional"))
    )
    (net (code "100") (name "Net-(VR1-S)") (class "Default")
      (node (ref "VR1") (pin "P$2") (pinfunction "S_P$2") (pintype "passive"))
      (node (ref "X1") (pin "3") (pinfunction "VO_3") (pintype "input"))
    )
    (net (code "101") (name "PWM1") (class "Default")
      (node (ref "B1") (pin "2") (pinfunction "2_2") (pintype "bidirectional"))
      (node (ref "PWM_RAIL") (pin "1") (pinfunction "1_1") (pintype "passive"))
    )
    (net (code "102") (name "PWM2") (class "Default")
      (node (ref "B1") (pin "3") (pinfunction "3_3") (pintype "bidirectional"))
      (node (ref "PWM_RAIL") (pin "2") (pinfunction "2_2") (pintype "passive"))
    )
    (net (code "103") (name "PWM3") (class "Default")
      (node (ref "B1") (pin "4") (pinfunction "4_4") (pintype "bidirectional"))
      (node (ref "PWM_RAIL") (pin "3") (pinfunction "3_3") (pintype "passive"))
    )
    (net (code "104") (name "PWM4") (class "Default")
      (node (ref "B1") (pin "5") (pinfunction "5_5") (pintype "bidirectional"))
      (node (ref "PWM_RAIL") (pin "4") (pinfunction "4_4") (pintype "passive"))
    )
    (net (code "105") (name "PWM5") (class "Default")
      (node (ref "B1") (pin "6") (pinfunction "6_6") (pintype "bidirectional"))
      (node (ref "PWM_RAIL") (pin "5") (pinfunction "5_5") (pintype "passive"))
    )
    (net (code "106") (name "PWM6") (class "Default")
      (node (ref "B1") (pin "7") (pinfunction "7_7") (pintype "bidirectional"))
      (node (ref "PWM_RAIL") (pin "6") (pinfunction "6_6") (pintype "passive"))
    )
    (net (code "107") (name "PWM7") (class "Default")
      (node (ref "B1") (pin "8") (pinfunction "8_8") (pintype "bidirectional"))
      (node (ref "PWM_RAIL") (pin "7") (pinfunction "7_7") (pintype "passive"))
    )
    (net (code "108") (name "PWM8") (class "Default")
      (node (ref "B1") (pin "9") (pinfunction "9_9") (pintype "bidirectional"))
      (node (ref "PWM_RAIL") (pin "8") (pinfunction "8_8") (pintype "passive"))
    )
    (net (code "109") (name "PWM9") (class "Default")
      (node (ref "B1") (pin "10") (pinfunction "10_10") (pintype "bidirectional"))
      (node (ref "IC2") (pin "11") (pinfunction "ENABLE_B_11") (pintype "input"))
      (node (ref "PWM_RAIL") (pin "9") (pinfunction "9_9") (pintype "passive"))
    )
    (net (code "110") (name "PWM10") (class "Default")
      (node (ref "B1") (pin "11") (pinfunction "11_11") (pintype "bidirectional"))
      (node (ref "IC2") (pin "6") (pinfunction "ENABLE_A_6") (pintype "input"))
      (node (ref "PWM_RAIL") (pin "10") (pinfunction "10_10") (pintype "passive"))
    )
    (net (code "111") (name "PWM11") (class "Default")
      (node (ref "B1") (pin "12") (pinfunction "12_12") (pintype "bidirectional"))
      (node (ref "IC1") (pin "11") (pinfunction "ENABLE_B_11") (pintype "input"))
      (node (ref "PWM_RAIL") (pin "11") (pinfunction "11_11") (pintype "passive"))
    )
    (net (code "112") (name "PWM12") (class "Default")
      (node (ref "B1") (pin "13") (pinfunction "13_13") (pintype "bidirectional"))
      (node (ref "IC1") (pin "6") (pinfunction "ENABLE_A_6") (pintype "input"))
      (node (ref "PWM_RAIL") (pin "12") (pinfunction "12_12") (pintype "passive"))
    )
    (net (code "113") (name "RF_TRANS") (class "Default")
      (node (ref "B1") (pin "38") (pinfunction "38_38") (pintype "bidirectional"))
      (node (ref "RF_TRANS") (pin "1") (pinfunction "1_1") (pintype "passive"))
    )
    (net (code "114") (name "SCL") (class "Default")
      (node (ref "B1") (pin "21") (pinfunction "21(SCL)_21") (pintype "bidirectional"))
      (node (ref "I2C_BUS_SCL") (pin "1") (pinfunction "1_1") (pintype "passive"))
      (node (ref "I2C_BUS_SCL") (pin "2") (pinfunction "2_2") (pintype "passive"))
      (node (ref "I2C_BUS_SCL") (pin "3") (pinfunction "3_3") (pintype "passive"))
      (node (ref "I2C_BUS_SCL") (pin "4") (pinfunction "4_4") (pintype "passive"))
      (node (ref "I2C_BUS_SCL") (pin "5") (pinfunction "5_5") (pintype "passive"))
      (node (ref "IMU") (pin "2") (pinfunction "2_2") (pintype "passive"))
      (node (ref "R1") (pin "2") (pinfunction "2_2") (pintype "passive"))
      (node (ref "R10") (pin "1") (pinfunction "1_1") (pintype "passive"))
      (node (ref "R16") (pin "1") (pinfunction "1_1") (pintype "passive"))
      (node (ref "R33") (pin "1") (pinfunction "1_1") (pintype "passive"))
      (node (ref "U2") (pin "P$26") (pinfunction "SCL_P$26") (pintype "bidirectional"))
      (node (ref "U3") (pin "5") (pinfunction "SCL_5") (pintype "bidirectional"))
      (node (ref "U5") (pin "5") (pinfunction "SCL_5") (pintype "bidirectional"))
    )
    (net (code "115") (name "SDA") (class "Default")
      (node (ref "B1") (pin "20") (pinfunction "20(SDA)_20") (pintype "bidirectional"))
      (node (ref "I2C_BUS_SDA") (pin "1") (pinfunction "1_1") (pintype "passive"))
      (node (ref "I2C_BUS_SDA") (pin "2") (pinfunction "2_2") (pintype "passive"))
      (node (ref "I2C_BUS_SDA") (pin "3") (pinfunction "3_3") (pintype "passive"))
      (node (ref "I2C_BUS_SDA") (pin "4") (pinfunction "4_4") (pintype "passive"))
      (node (ref "I2C_BUS_SDA") (pin "5") (pinfunction "5_5") (pintype "passive"))
      (node (ref "IMU") (pin "3") (pinfunction "3_3") (pintype "passive"))
      (node (ref "R15") (pin "1") (pinfunction "1_1") (pintype "passive"))
      (node (ref "R2") (pin "2") (pinfunction "2_2") (pintype "passive"))
      (node (ref "R32") (pin "1") (pinfunction "1_1") (pintype "passive"))
      (node (ref "R9") (pin "1") (pinfunction "1_1") (pintype "passive"))
      (node (ref "U2") (pin "P$27") (pinfunction "SDA_P$27") (pintype "bidirectional"))
      (node (ref "U3") (pin "4") (pinfunction "SDA_4") (pintype "bidirectional"))
      (node (ref "U5") (pin "4") (pinfunction "SDA_4") (pintype "bidirectional"))
    )
    (net (code "116") (name "SW1") (class "Default")
      (node (ref "B1") (pin "48") (pinfunction "48_48") (pintype "bidirectional"))
      (node (ref "S15") (pin "P") (pinfunction "P_P") (pintype "passive"))
    )
    (net (code "117") (name "SW2") (class "Default")
      (node (ref "B1") (pin "49") (pinfunction "49_49") (pintype "bidirectional"))
      (node (ref "S6") (pin "P") (pinfunction "P_P") (pintype "passive"))
    )
    (net (code "118") (name "SW3") (class "Default")
      (node (ref "B1") (pin "50") (pinfunction "50_50") (pintype "bidirectional"))
      (node (ref "S7") (pin "P") (pinfunction "P_P") (pintype "passive"))
    )
    (net (code "119") (name "SW4") (class "Default")
      (node (ref "B1") (pin "51") (pinfunction "51_51") (pintype "bidirectional"))
      (node (ref "S8") (pin "P") (pinfunction "P_P") (pintype "passive"))
    )
    (net (code "120") (name "SW5") (class "Default")
      (node (ref "B1") (pin "52") (pinfunction "52_52") (pintype "bidirectional"))
      (node (ref "S9") (pin "P") (pinfunction "P_P") (pintype "passive"))
    )
    (net (code "121") (name "SW6") (class "Default")
      (node (ref "B1") (pin "53") (pinfunction "53_53") (pintype "bidirectional"))
      (node (ref "S10") (pin "P") (pinfunction "P_P") (pintype "passive"))
    )
    (net (code "122") (name "VOUT1") (class "Default")
      (node (ref "DAC_RAIL") (pin "1") (pinfunction "1_1") (pintype "passive"))
      (node (ref "U3") (pin "1") (pinfunction "VOUT_1") (pintype "output"))
    )
    (net (code "123") (name "VOUT2") (class "Default")
      (node (ref "DAC_RAIL") (pin "2") (pinfunction "2_2") (pintype "passive"))
      (node (ref "U5") (pin "1") (pinfunction "VOUT_1") (pintype "output"))
    )
    (net (code "124") (name "unconnected-(B1-5V-Pad5V@0)") (class "Default")
      (node (ref "B1") (pin "5V@0") (pinfunction "5V_5V@0") (pintype "bidirectional"))
    )
    (net (code "125") (name "unconnected-(B1-5V-Pad5V@1)") (class "Default")
      (node (ref "B1") (pin "5V@1") (pinfunction "5V_5V@1") (pintype "bidirectional"))
    )
    (net (code "126") (name "unconnected-(B1-5V-Pad5V@2)") (class "Default")
      (node (ref "B1") (pin "5V@2") (pinfunction "5V_5V@2") (pintype "bidirectional"))
    )
    (net (code "127") (name "unconnected-(B1-PadAREF)") (class "Default")
      (node (ref "B1") (pin "AREF") (pinfunction "AREF_AREF") (pintype "bidirectional"))
    )
    (net (code "128") (name "unconnected-(B1-PadRESET)") (class "Default")
      (node (ref "B1") (pin "RESET") (pinfunction "RESET_RESET") (pintype "bidirectional"))
    )
    (net (code "129") (name "unconnected-(BLE-Pad1)") (class "Default")
      (node (ref "BLE") (pin "1") (pinfunction "1_1") (pintype "passive"))
    )
    (net (code "130") (name "unconnected-(BLE-Pad3)") (class "Default")
      (node (ref "BLE") (pin "3") (pinfunction "3_3") (pintype "passive"))
    )
    (net (code "131") (name "unconnected-(BLE-Pad8)") (class "Default")
      (node (ref "BLE") (pin "8") (pinfunction "8_8") (pintype "passive"))
    )
    (net (code "132") (name "unconnected-(BT-Pad1)") (class "Default")
      (node (ref "BT") (pin "1") (pinfunction "1_1") (pintype "passive"))
    )
    (net (code "133") (name "unconnected-(BT-Pad6)") (class "Default")
      (node (ref "BT") (pin "6") (pinfunction "6_6") (pintype "passive"))
    )
    (net (code "134") (name "unconnected-(D1-A-Pad1)") (class "Default")
      (node (ref "D1") (pin "1") (pinfunction "A_1") (pintype "passive"))
    )
    (net (code "135") (name "unconnected-(D3-A-Pad1)") (class "Default")
      (node (ref "D3") (pin "1") (pinfunction "A_1") (pintype "passive"))
    )
    (net (code "136") (name "unconnected-(GPS-Pad5)") (class "Default")
      (node (ref "GPS") (pin "5") (pinfunction "5_5") (pintype "passive"))
    )
    (net (code "137") (name "unconnected-(GPS-Pad6)") (class "Default")
      (node (ref "GPS") (pin "6") (pinfunction "6_6") (pintype "passive"))
    )
    (net (code "138") (name "unconnected-(GPS-Pad7)") (class "Default")
      (node (ref "GPS") (pin "7") (pinfunction "7_7") (pintype "passive"))
    )
    (net (code "139") (name "unconnected-(GPS-Pad8)") (class "Default")
      (node (ref "GPS") (pin "8") (pinfunction "8_8") (pintype "passive"))
    )
    (net (code "140") (name "unconnected-(GPS-Pad9)") (class "Default")
      (node (ref "GPS") (pin "9") (pinfunction "9_9") (pintype "passive"))
    )
    (net (code "141") (name "unconnected-(IC3-CB-Pad3)") (class "Default")
      (node (ref "IC3") (pin "3") (pinfunction "CB_3") (pintype "input"))
    )
    (net (code "142") (name "unconnected-(IC3-ON-Pad7)") (class "Default")
      (node (ref "IC3") (pin "7") (pinfunction "ON_7") (pintype "passive"))
    )
    (net (code "143") (name "unconnected-(IMU-Pad1)") (class "Default")
      (node (ref "IMU") (pin "1") (pinfunction "1_1") (pintype "passive"))
    )
    (net (code "144") (name "unconnected-(IMU-Pad5)") (class "Default")
      (node (ref "IMU") (pin "5") (pinfunction "5_5") (pintype "passive"))
    )
    (net (code "145") (name "unconnected-(RF_REC-Pad2)") (class "Default")
      (node (ref "RF_REC") (pin "2") (pinfunction "2_2") (pintype "passive"))
    )
    (net (code "146") (name "unconnected-(S1-Pad2)") (class "Default")
      (node (ref "S1") (pin "2") (pinfunction "2_2") (pintype "passive"))
    )
    (net (code "147") (name "unconnected-(S1-Pad4)") (class "Default")
      (node (ref "S1") (pin "4") (pinfunction "4_4") (pintype "passive"))
    )
    (net (code "148") (name "unconnected-(S2-Pad2)") (class "Default")
      (node (ref "S2") (pin "2") (pinfunction "2_2") (pintype "passive"))
    )
    (net (code "149") (name "unconnected-(S2-Pad4)") (class "Default")
      (node (ref "S2") (pin "4") (pinfunction "4_4") (pintype "passive"))
    )
    (net (code "150") (name "unconnected-(S3-Pad2)") (class "Default")
      (node (ref "S3") (pin "2") (pinfunction "2_2") (pintype "passive"))
    )
    (net (code "151") (name "unconnected-(S3-Pad4)") (class "Default")
      (node (ref "S3") (pin "4") (pinfunction "4_4") (pintype "passive"))
    )
    (net (code "152") (name "unconnected-(S4-Pad2)") (class "Default")
      (node (ref "S4") (pin "2") (pinfunction "2_2") (pintype "passive"))
    )
    (net (code "153") (name "unconnected-(S4-Pad4)") (class "Default")
      (node (ref "S4") (pin "4") (pinfunction "4_4") (pintype "passive"))
    )
    (net (code "154") (name "unconnected-(S5-Pad2)") (class "Default")
      (node (ref "S5") (pin "2") (pinfunction "2_2") (pintype "passive"))
    )
    (net (code "155") (name "unconnected-(S5-Pad4)") (class "Default")
      (node (ref "S5") (pin "4") (pinfunction "4_4") (pintype "passive"))
    )
    (net (code "156") (name "unconnected-(U2-COM4-PadP$6)") (class "Default")
      (node (ref "U2") (pin "P$6") (pinfunction "COM4_P$6") (pintype "bidirectional"))
    )
    (net (code "157") (name "unconnected-(U2-COM5-PadP$7)") (class "Default")
      (node (ref "U2") (pin "P$7") (pinfunction "COM5_P$7") (pintype "bidirectional"))
    )
    (net (code "158") (name "unconnected-(U2-COM6-PadP$8)") (class "Default")
      (node (ref "U2") (pin "P$8") (pinfunction "COM6_P$8") (pintype "bidirectional"))
    )
    (net (code "159") (name "unconnected-(U2-COM7-PadP$9)") (class "Default")
      (node (ref "U2") (pin "P$9") (pinfunction "COM7_P$9") (pintype "bidirectional"))
    )
    (net (code "160") (name "unconnected-(U2-ROW15{slash}K13{slash}INT-PadP$10)") (class "Default")
      (node (ref "U2") (pin "P$10") (pinfunction "ROW15/K13/INT_P$10") (pintype "bidirectional"))
    )
    (net (code "161") (name "unconnected-(WIFI-Pad4)") (class "Default")
      (node (ref "WIFI") (pin "4") (pinfunction "4_4") (pintype "passive"))
    )
    (net (code "162") (name "unconnected-(XBEE-AD0{slash}DIO0-Pad20)") (class "Default")
      (node (ref "XBEE") (pin "20") (pinfunction "AD0/DIO0_20") (pintype "bidirectional"))
    )
    (net (code "163") (name "unconnected-(XBEE-AD1{slash}DIO1-Pad19)") (class "Default")
      (node (ref "XBEE") (pin "19") (pinfunction "AD1/DIO1_19") (pintype "bidirectional"))
    )
    (net (code "164") (name "unconnected-(XBEE-AD2{slash}DIO2-Pad18)") (class "Default")
      (node (ref "XBEE") (pin "18") (pinfunction "AD2/DIO2_18") (pintype "bidirectional"))
    )
    (net (code "165") (name "unconnected-(XBEE-AD3{slash}DIO3-Pad17)") (class "Default")
      (node (ref "XBEE") (pin "17") (pinfunction "AD3/DIO3_17") (pintype "bidirectional"))
    )
    (net (code "166") (name "unconnected-(XBEE-AD4{slash}DIO4-Pad11)") (class "Default")
      (node (ref "XBEE") (pin "11") (pinfunction "AD4/DIO4_11") (pintype "bidirectional"))
    )
    (net (code "167") (name "unconnected-(XBEE-ASC{slash}AD5{slash}DIO5-Pad15)") (class "Default")
      (node (ref "XBEE") (pin "15") (pinfunction "ASC/AD5/DIO5_15") (pintype "bidirectional"))
    )
    (net (code "168") (name "unconnected-(XBEE-CTS{slash}DIO7-Pad12)") (class "Default")
      (node (ref "XBEE") (pin "12") (pinfunction "CTS/DIO7_12") (pintype "bidirectional"))
    )
    (net (code "169") (name "unconnected-(XBEE-DO8-Pad4)") (class "Default")
      (node (ref "XBEE") (pin "4") (pinfunction "DO8_4") (pintype "output"))
    )
    (net (code "170") (name "unconnected-(XBEE-DTR{slash}DI8-Pad9)") (class "Default")
      (node (ref "XBEE") (pin "9") (pinfunction "DTR/DI8_9") (pintype "input"))
    )
    (net (code "171") (name "unconnected-(XBEE-ON{slash}SLEEP-Pad13)") (class "Default")
      (node (ref "XBEE") (pin "13") (pinfunction "ON/SLEEP_13") (pintype "output"))
    )
    (net (code "172") (name "unconnected-(XBEE-PWM0{slash}RSSI-Pad6)") (class "Default")
      (node (ref "XBEE") (pin "6") (pinfunction "PWM0/RSSI_6") (pintype "output"))
    )
    (net (code "173") (name "unconnected-(XBEE-PWM1-Pad7)") (class "Default")
      (node (ref "XBEE") (pin "7") (pinfunction "PWM1_7") (pintype "output"))
    )
    (net (code "174") (name "unconnected-(XBEE-RESERVED-Pad8)") (class "Default")
      (node (ref "XBEE") (pin "8") (pinfunction "RESERVED_8") (pintype "no_connect"))
    )
    (net (code "175") (name "unconnected-(XBEE-RESET-Pad5)") (class "Default")
      (node (ref "XBEE") (pin "5") (pinfunction "RESET_5") (pintype "input"))
    )
    (net (code "176") (name "unconnected-(XBEE-RTS{slash}AD6{slash}DIO6-Pad16)") (class "Default")
      (node (ref "XBEE") (pin "16") (pinfunction "RTS/AD6/DIO6_16") (pintype "bidirectional"))
    )
    (net (code "177") (name "unconnected-(XBEE-VREF-Pad14)") (class "Default")
      (node (ref "XBEE") (pin "14") (pinfunction "VREF_14") (pintype "input"))
    )
  )
)
